# LKS2024_ESP_ACController_v66.net
KiCad netlist of a schematic drawn in EAGLE
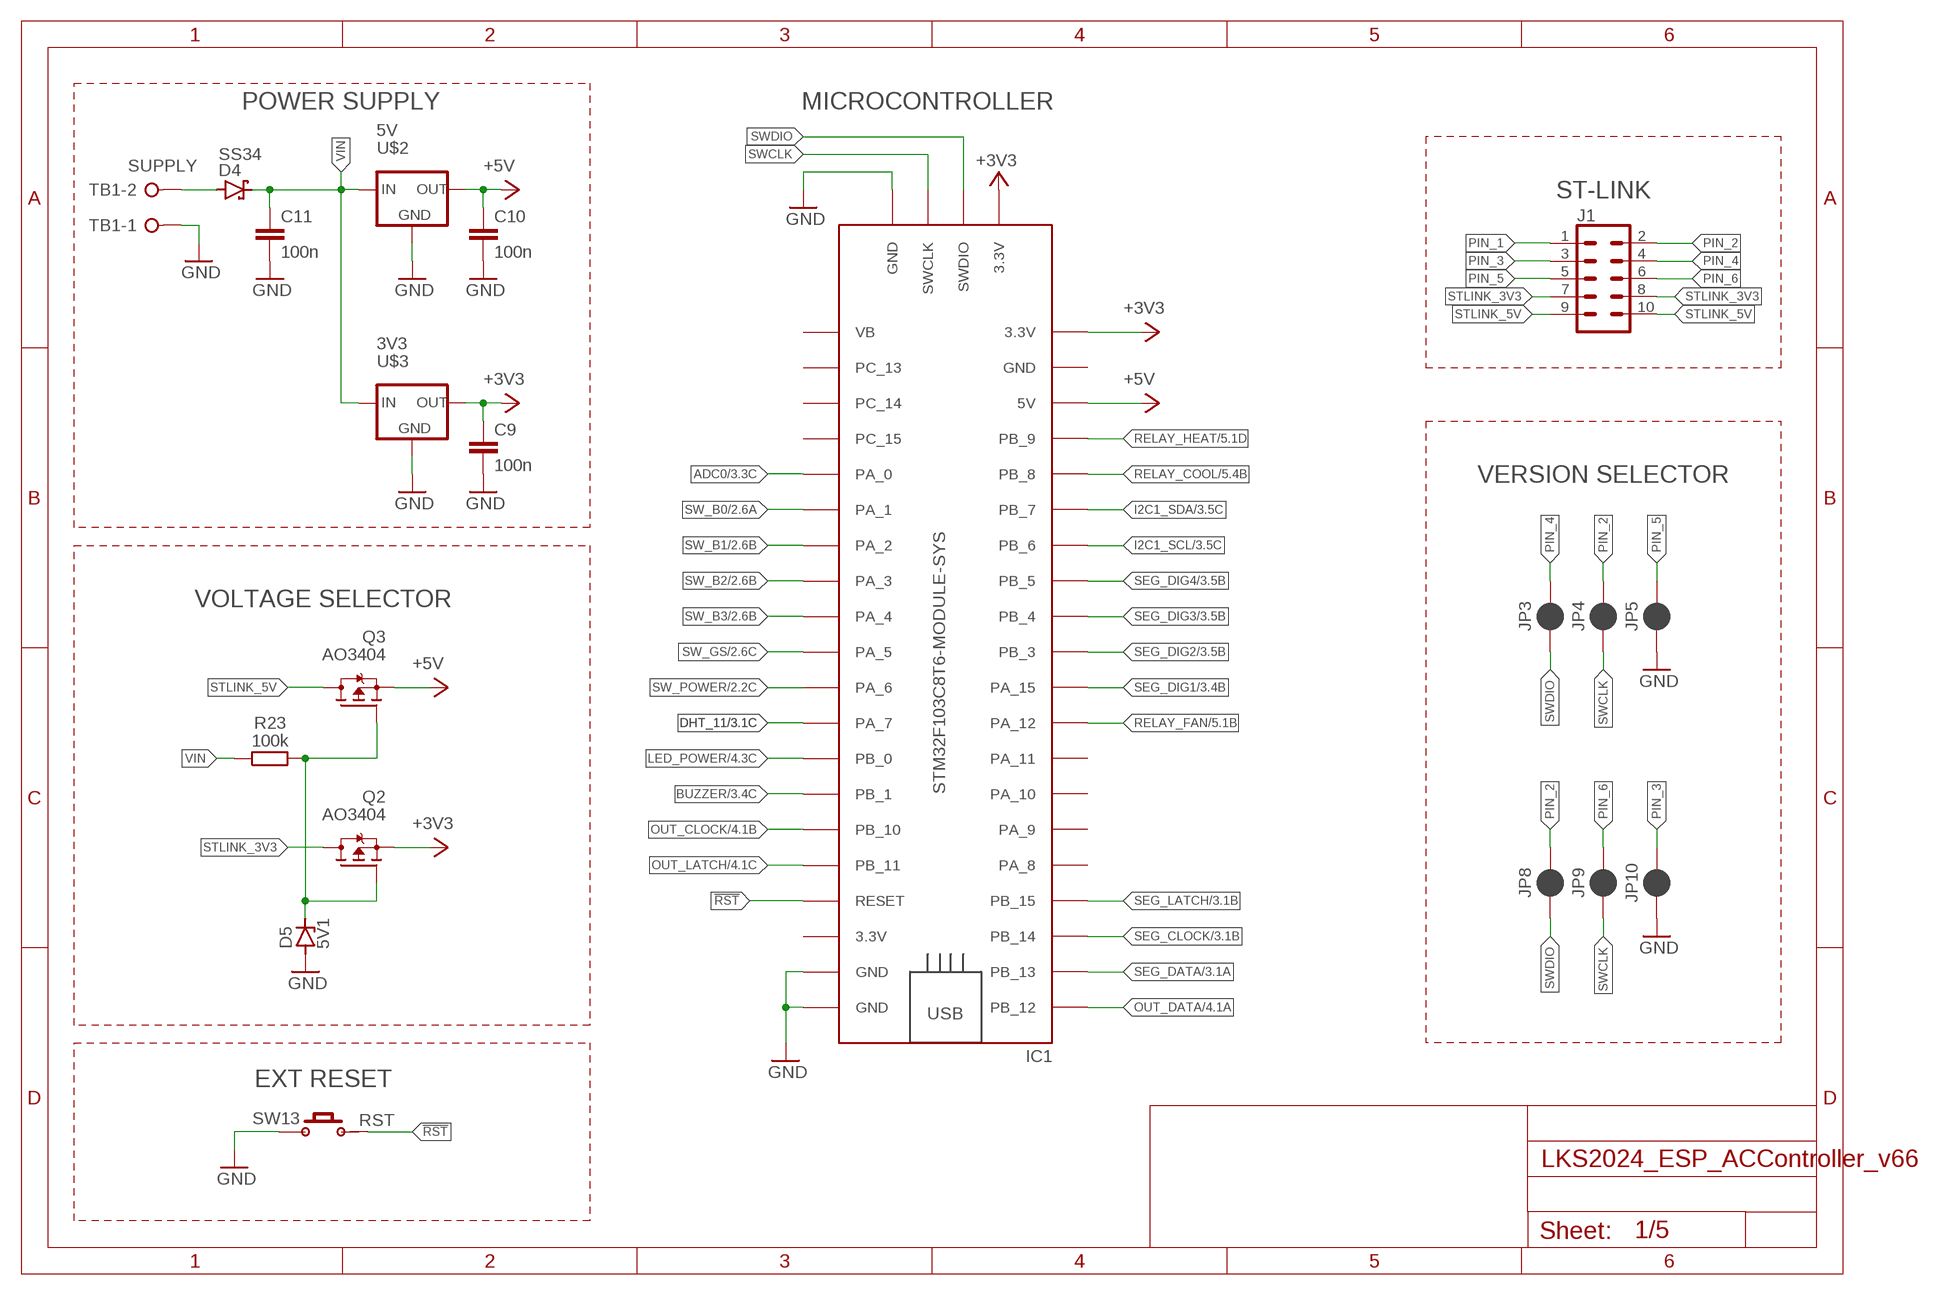
[diagram p0: schematic, sheet 1]
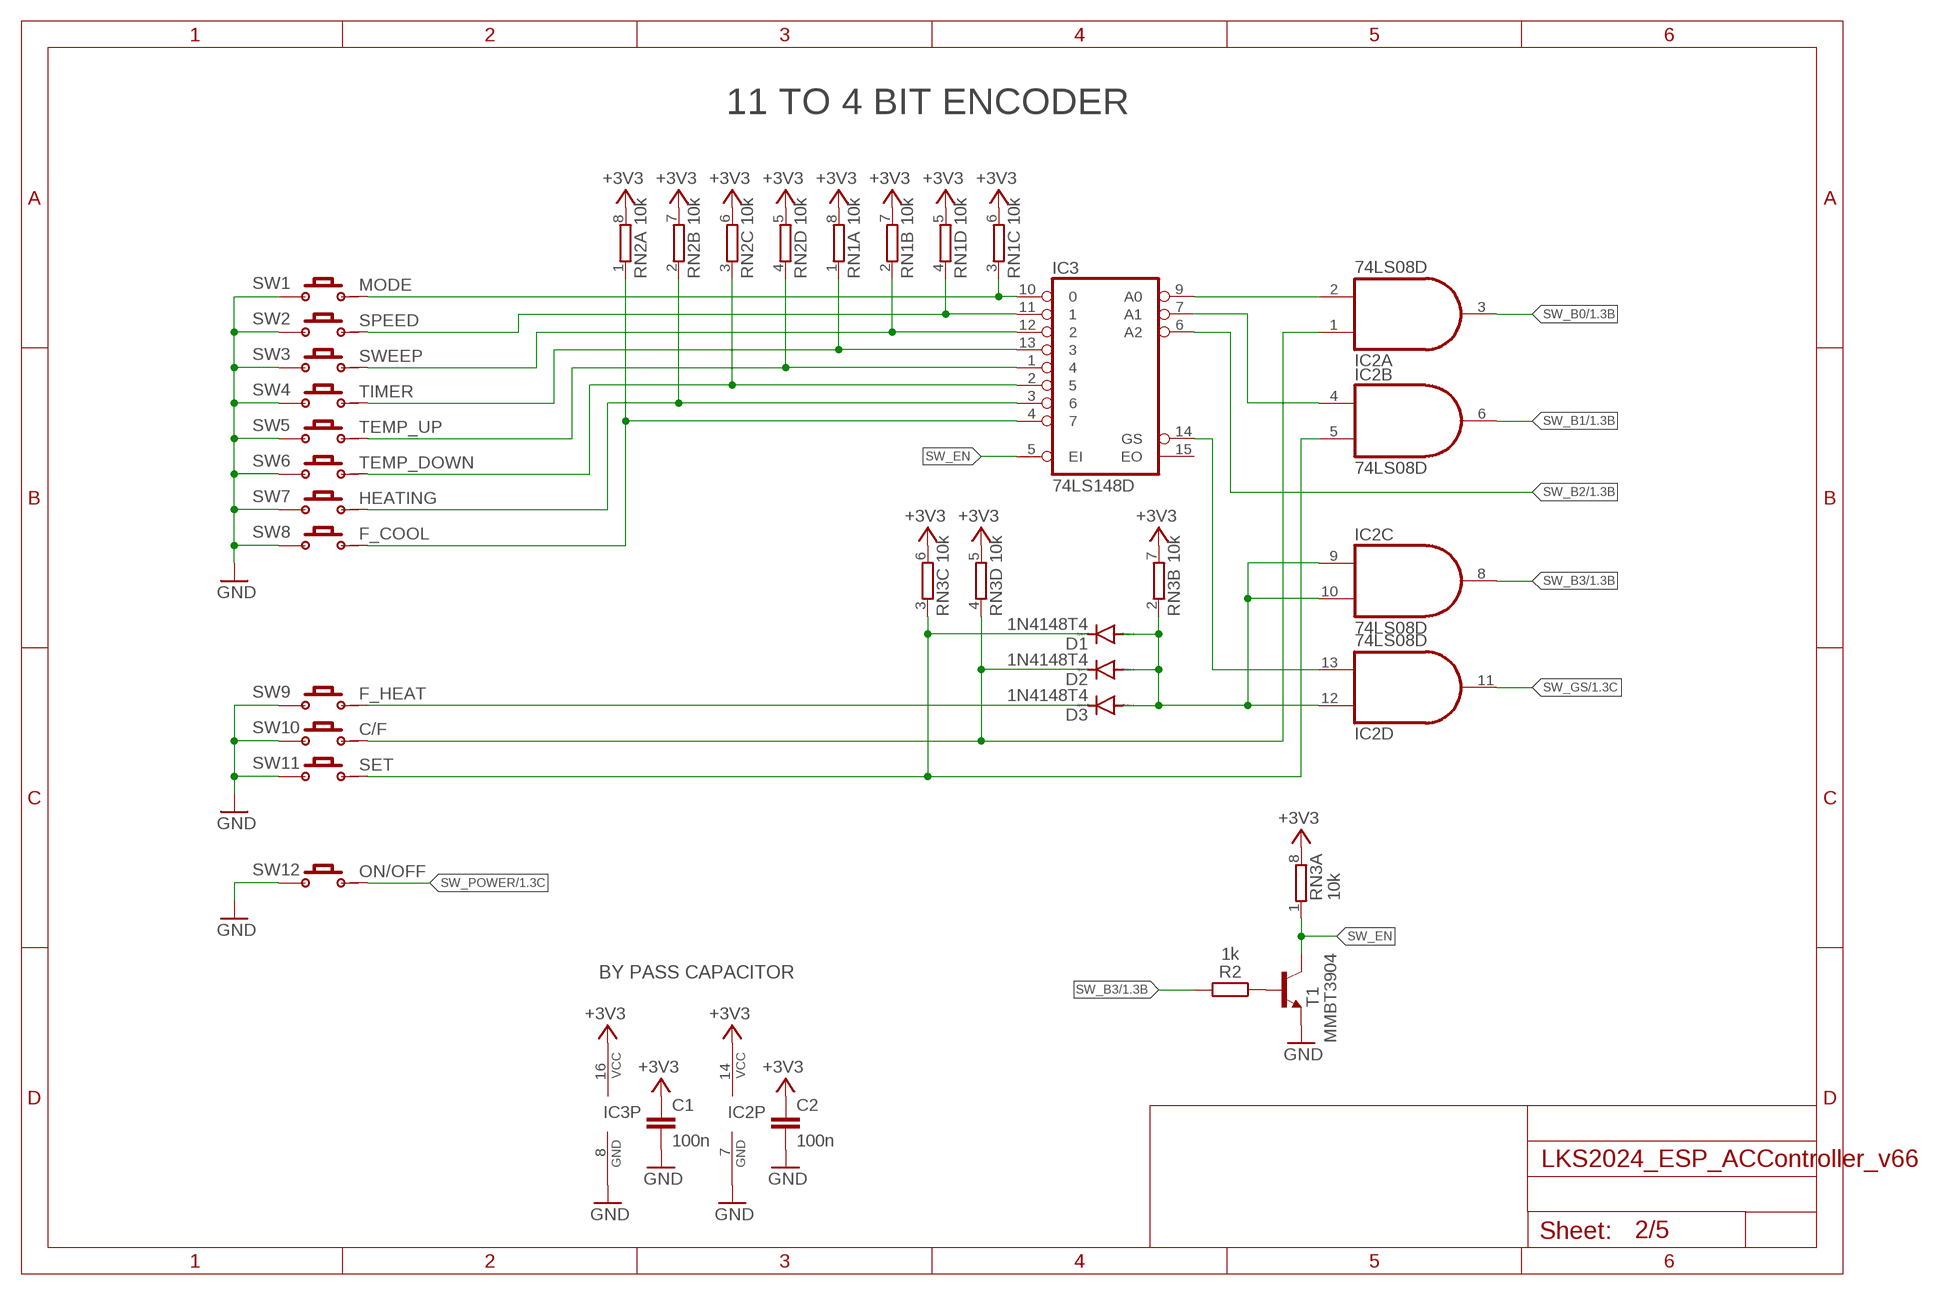
[diagram p1: schematic, sheet 2]
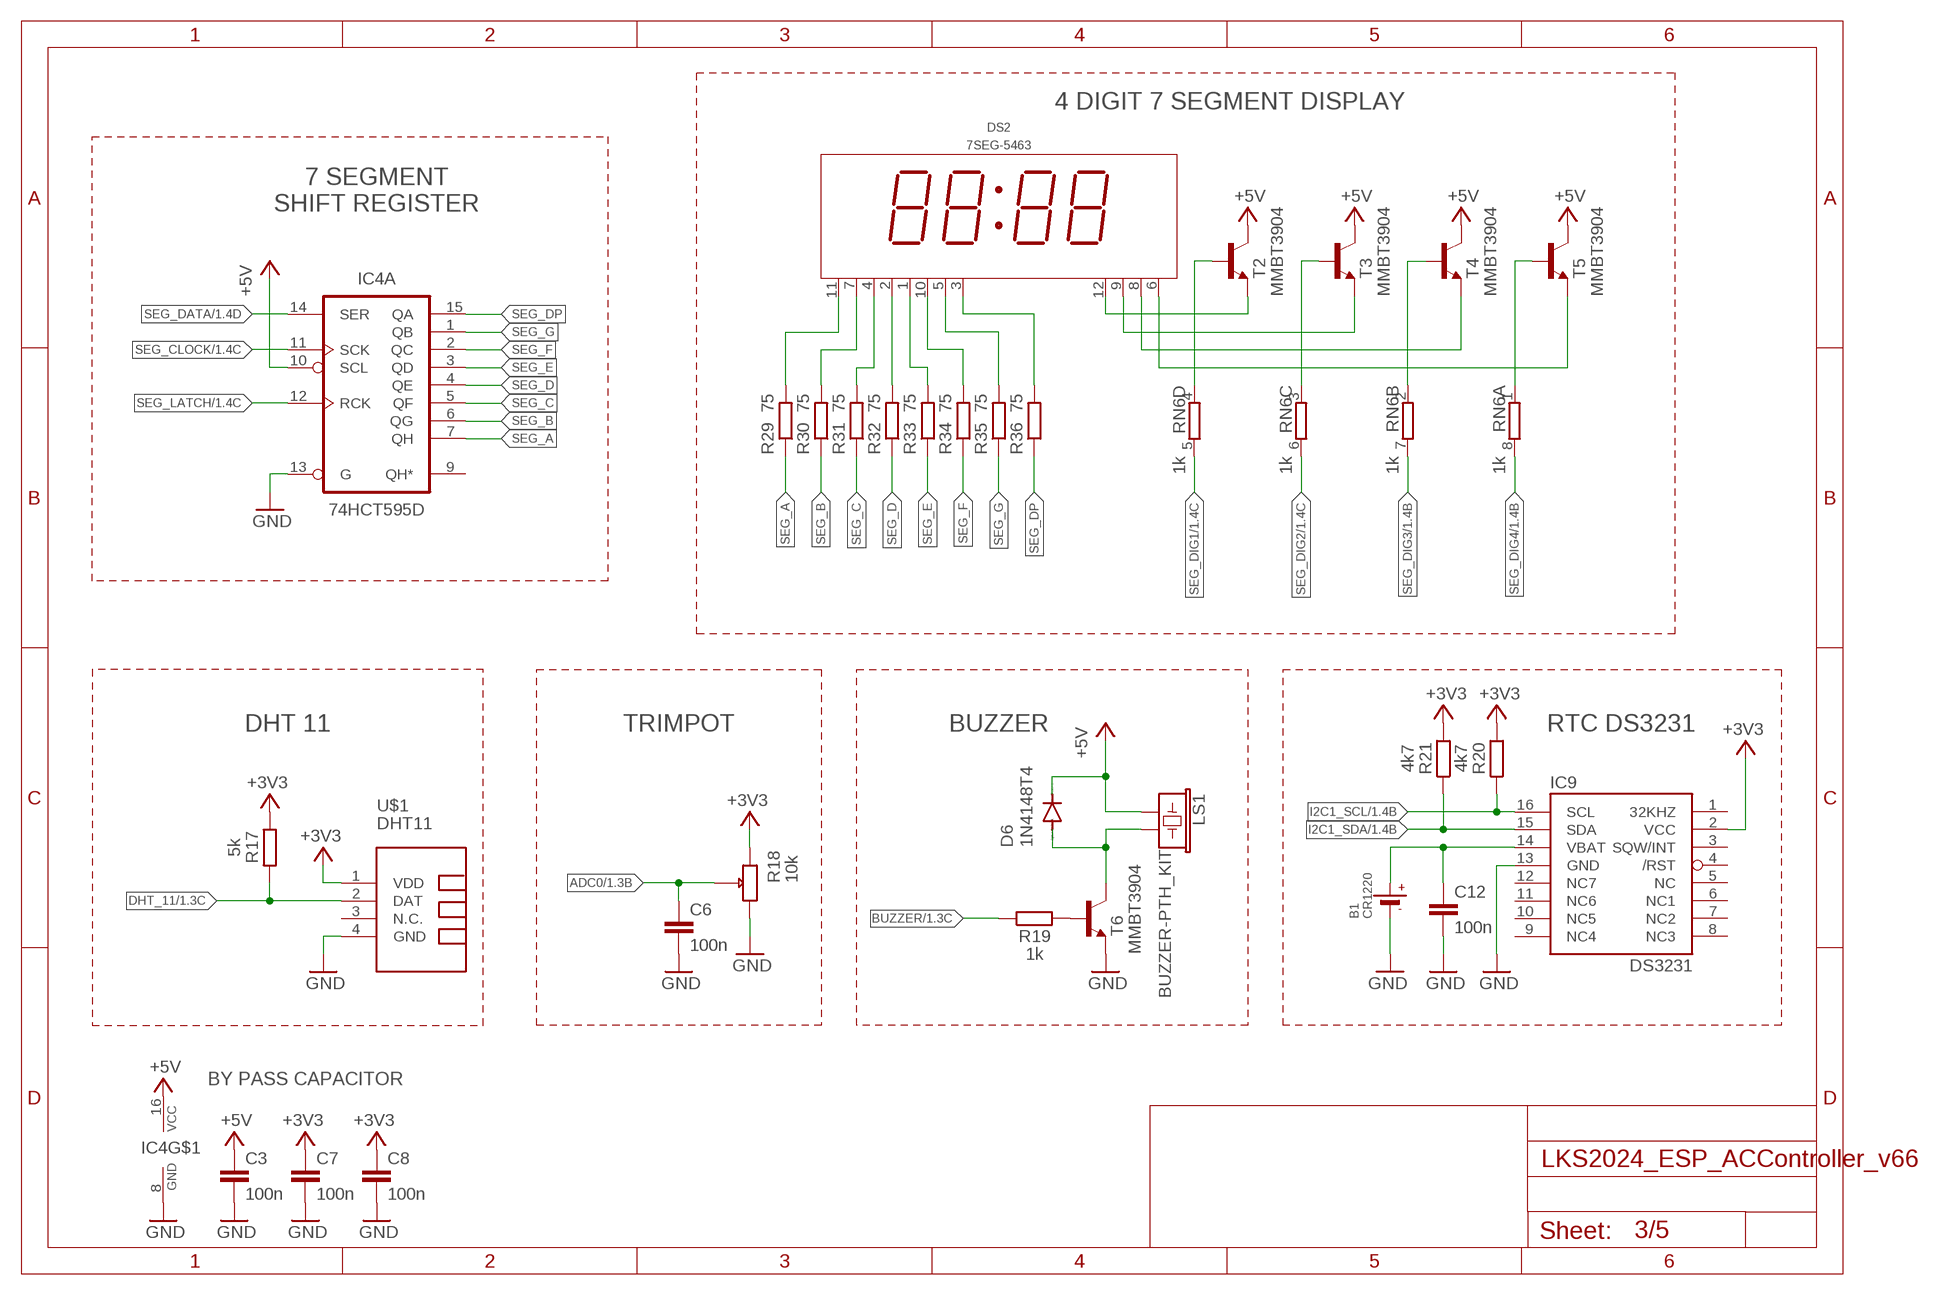
[diagram p2: schematic, sheet 3]
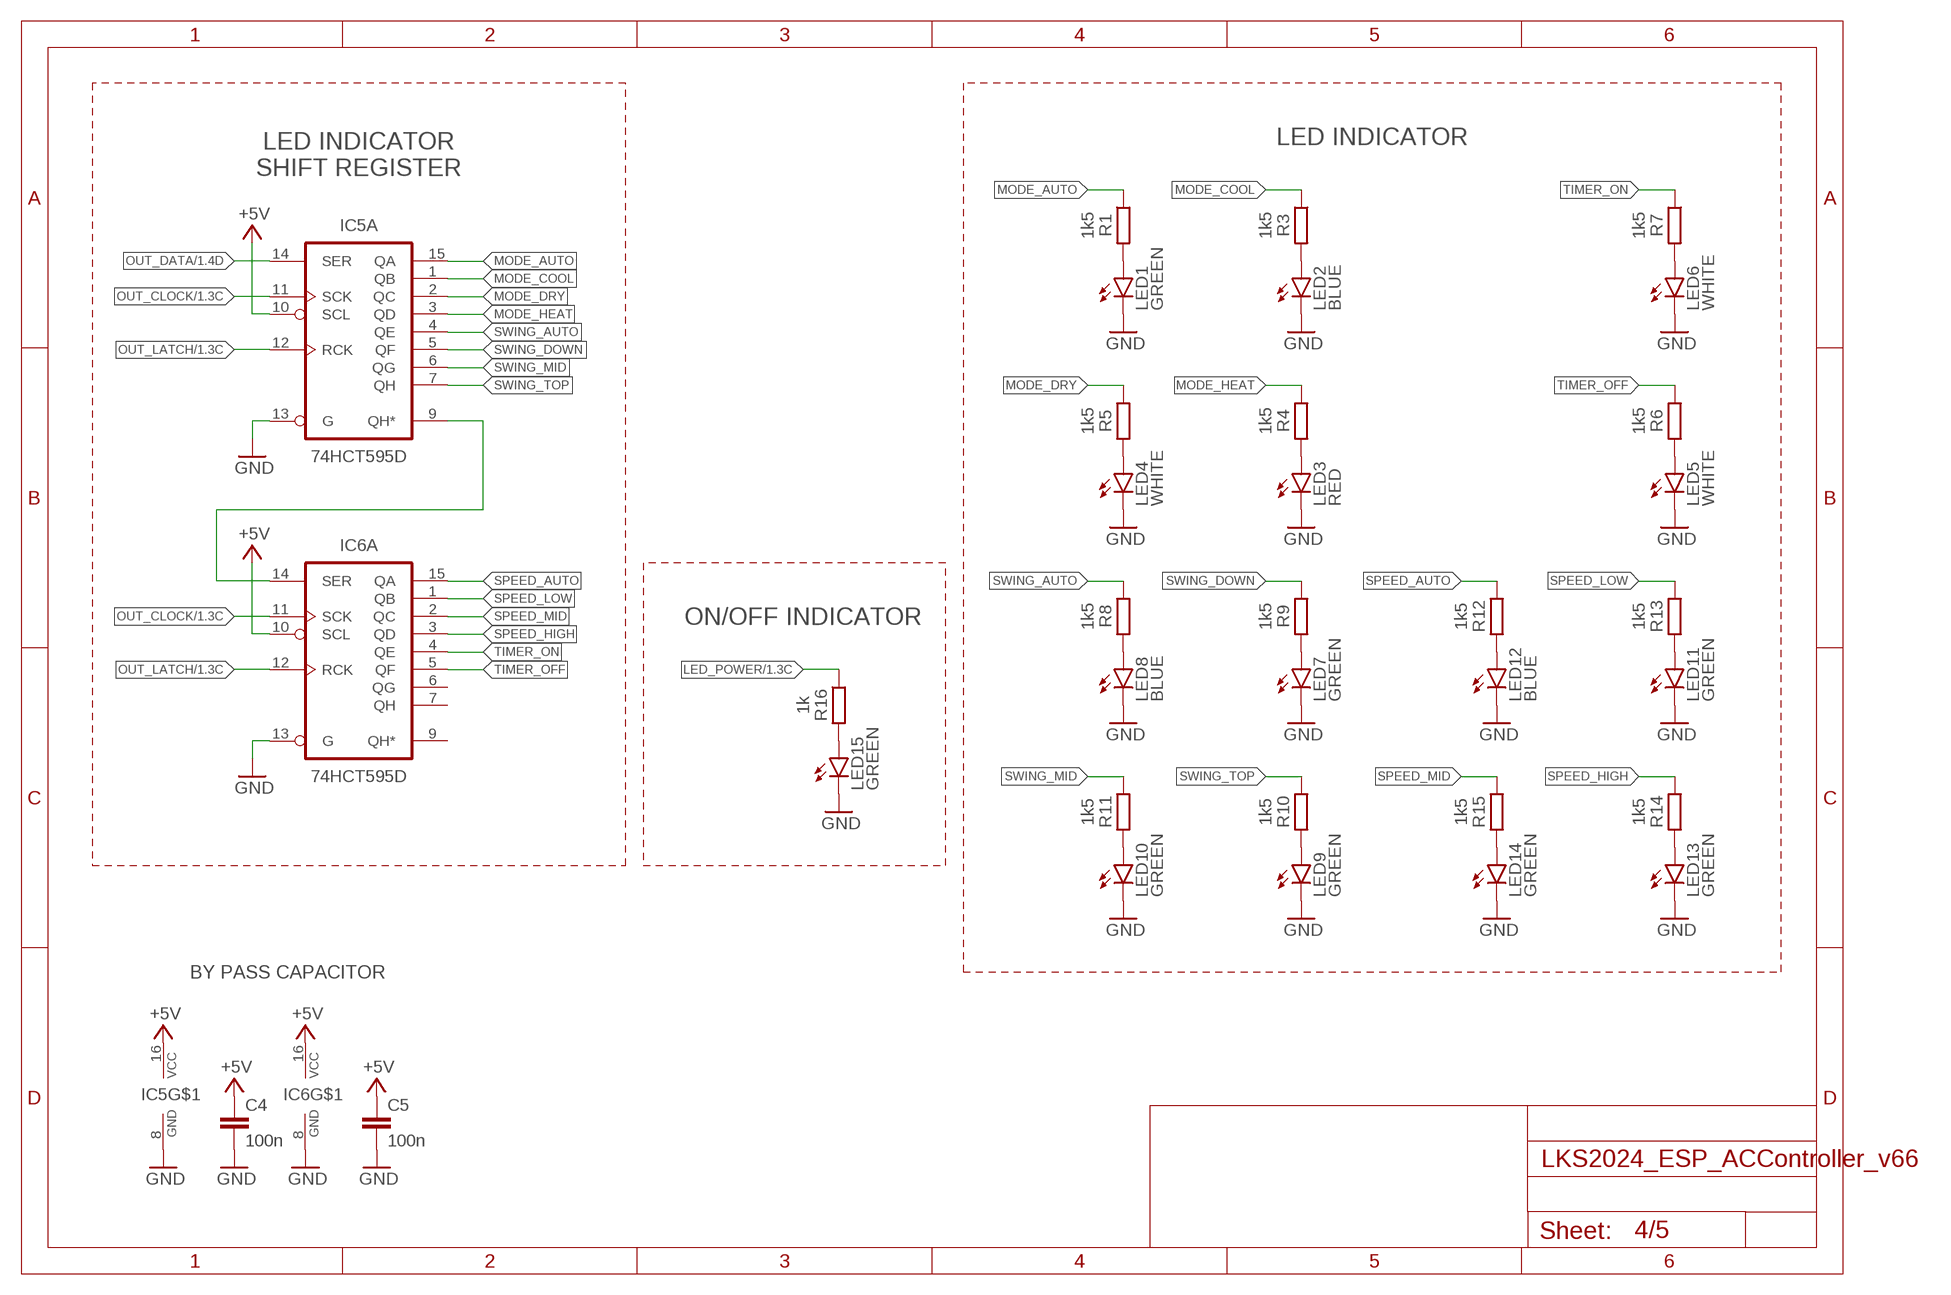
[diagram p3: schematic, sheet 4]
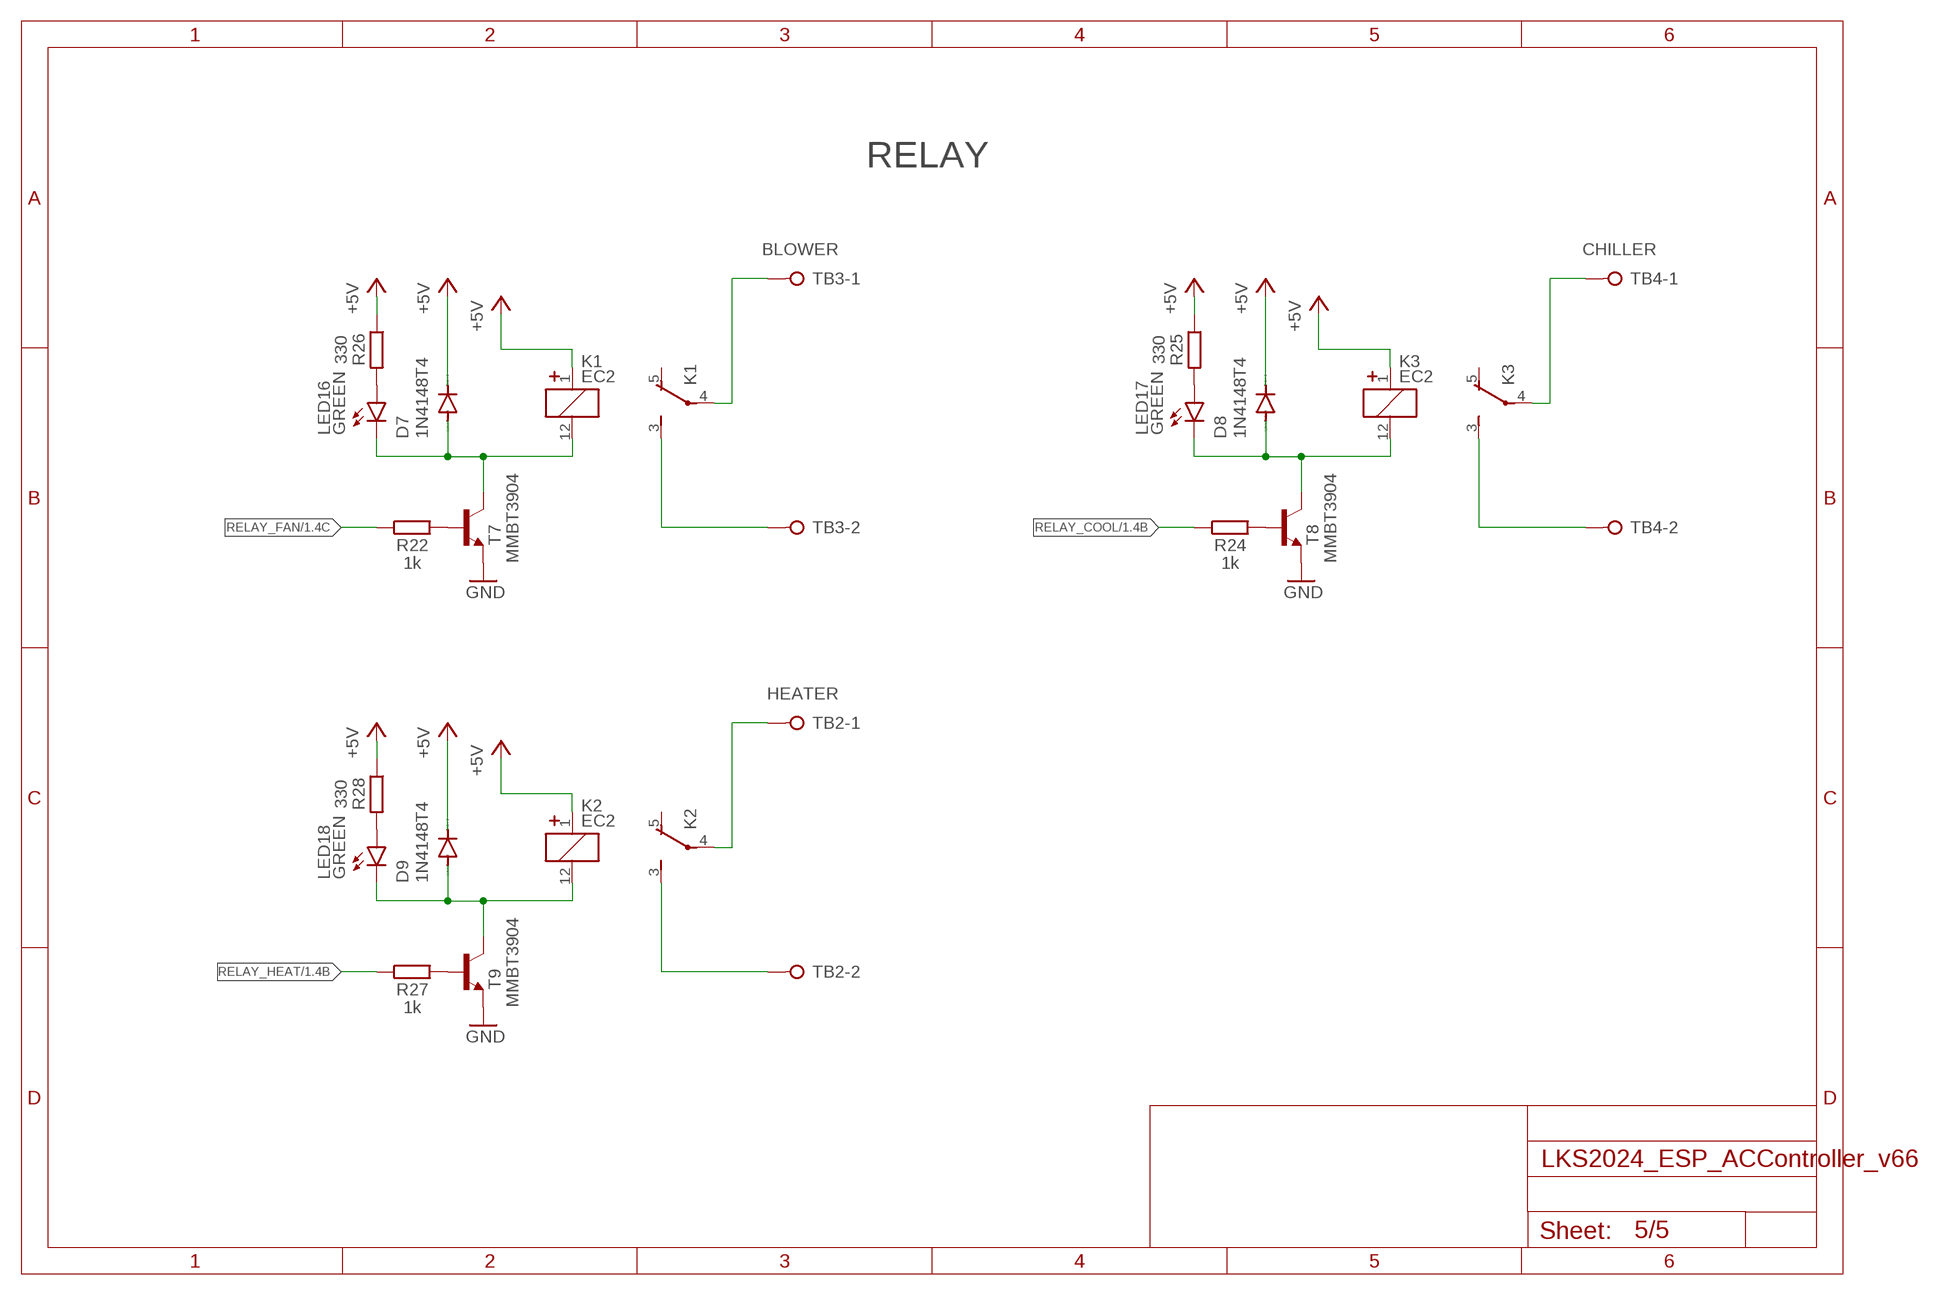
[diagram p4: schematic, sheet 5]

(export (version "E")
  (design (tool "Eeschema 10.0.6"))
  (components
    (comp (ref "D7")
      (value "1N4148T4")
      (footprint "eagle-import:SOD123")
      (libsource (lib "eagle-import") (part "1N4148T4"))
    )
    (comp (ref "D8")
      (value "1N4148T4")
      (footprint "eagle-import:SOD123")
      (libsource (lib "eagle-import") (part "1N4148T4"))
    )
    (comp (ref "D9")
      (value "1N4148T4")
      (footprint "eagle-import:SOD123")
      (libsource (lib "eagle-import") (part "1N4148T4"))
    )
    (comp (ref "K1")
      (value "EC2")
      (footprint "eagle-import:EC2")
      (libsource (lib "eagle-import") (part "EC2"))
    )
    (comp (ref "K2")
      (value "EC2")
      (footprint "eagle-import:EC2")
      (libsource (lib "eagle-import") (part "EC2"))
    )
    (comp (ref "K3")
      (value "EC2")
      (footprint "eagle-import:EC2")
      (libsource (lib "eagle-import") (part "EC2"))
    )
    (comp (ref "LED16")
      (value "GREEN")
      (footprint "eagle-import:CHIPLED_1206")
      (libsource (lib "eagle-import") (part "LEDCHIPLED_1206"))
    )
    (comp (ref "LED17")
      (value "GREEN")
      (footprint "eagle-import:CHIPLED_1206")
      (libsource (lib "eagle-import") (part "LEDCHIPLED_1206"))
    )
    (comp (ref "LED18")
      (value "GREEN")
      (footprint "eagle-import:CHIPLED_1206")
      (libsource (lib "eagle-import") (part "LEDCHIPLED_1206"))
    )
    (comp (ref "R22")
      (value "1k")
      (footprint "eagle-import:R0805")
      (libsource (lib "eagle-import") (part "R-EU_R0805"))
    )
    (comp (ref "R24")
      (value "1k")
      (footprint "eagle-import:R0805")
      (libsource (lib "eagle-import") (part "R-EU_R0805"))
    )
    (comp (ref "R25")
      (value "330")
      (footprint "eagle-import:R0805")
      (libsource (lib "eagle-import") (part "R-EU_R0805"))
    )
    (comp (ref "R26")
      (value "330")
      (footprint "eagle-import:R0805")
      (libsource (lib "eagle-import") (part "R-EU_R0805"))
    )
    (comp (ref "R27")
      (value "1k")
      (footprint "eagle-import:R0805")
      (libsource (lib "eagle-import") (part "R-EU_R0805"))
    )
    (comp (ref "R28")
      (value "330")
      (footprint "eagle-import:R0805")
      (libsource (lib "eagle-import") (part "R-EU_R0805"))
    )
    (comp (ref "T7")
      (value "MMBT3904")
      (footprint "eagle-import:SOT23-BEC")
      (libsource (lib "eagle-import") (part "MMBT3904SOT23-BEC"))
    )
    (comp (ref "T8")
      (value "MMBT3904")
      (footprint "eagle-import:SOT23-BEC")
      (libsource (lib "eagle-import") (part "MMBT3904SOT23-BEC"))
    )
    (comp (ref "T9")
      (value "MMBT3904")
      (footprint "eagle-import:SOT23-BEC")
      (libsource (lib "eagle-import") (part "MMBT3904SOT23-BEC"))
    )
    (comp (ref "TB2")
      (value "HEATER")
      (footprint "eagle-import:MSTBA2")
      (libsource (lib "eagle-import") (part "TERMINAL-BLOK-90"))
    )
    (comp (ref "TB3")
      (value "BLOWER")
      (footprint "eagle-import:MSTBA2")
      (libsource (lib "eagle-import") (part "TERMINAL-BLOK-90"))
    )
    (comp (ref "TB4")
      (value "CHILLER")
      (footprint "eagle-import:MSTBA2")
      (libsource (lib "eagle-import") (part "TERMINAL-BLOK-90"))
    )
    (comp (ref "C9")
      (value "100n")
      (footprint "eagle-import:C0805")
      (libsource (lib "eagle-import") (part "C-EUC0805"))
    )
    (comp (ref "C10")
      (value "100n")
      (footprint "eagle-import:C0805")
      (libsource (lib "eagle-import") (part "C-EUC0805"))
    )
    (comp (ref "C11")
      (value "100n")
      (footprint "eagle-import:C0805")
      (libsource (lib "eagle-import") (part "C-EUC0805"))
    )
    (comp (ref "D4")
      (value "SS34")
      (footprint "eagle-import:SMA")
      (libsource (lib "eagle-import") (part "SS34SMA"))
    )
    (comp (ref "D5")
      (value "5V1")
      (footprint "eagle-import:SOD80C")
      (libsource (lib "eagle-import") (part "ZENER-DIODESOD80C"))
    )
    (comp (ref "IC1")
      (value "STM32F103C8T6-MODULE-SYS")
      (footprint "eagle-import:STM32F103C8T6-MODULE-SYS")
      (libsource (lib "eagle-import") (part "STM32F103C8T6-MODULE-SYS"))
    )
    (comp (ref "J1")
      (value "CONN_05X2ML10L")
      (footprint "eagle-import:ML10L")
      (libsource (lib "eagle-import") (part "CONN_05X2ML10L"))
    )
    (comp (ref "JP3")
      (value "JUMPER-SMT_2_NC_PASTE_SILK")
      (footprint "eagle-import:SMT-JUMPER_2_NC_PASTE_SILK")
      (libsource (lib "eagle-import") (part "JUMPER-SMT_2_NC_PASTE_SILK"))
    )
    (comp (ref "JP4")
      (value "JUMPER-SMT_2_NC_PASTE_SILK")
      (footprint "eagle-import:SMT-JUMPER_2_NC_PASTE_SILK")
      (libsource (lib "eagle-import") (part "JUMPER-SMT_2_NC_PASTE_SILK"))
    )
    (comp (ref "JP5")
      (value "JUMPER-SMT_2_NC_PASTE_SILK")
      (footprint "eagle-import:SMT-JUMPER_2_NC_PASTE_SILK")
      (libsource (lib "eagle-import") (part "JUMPER-SMT_2_NC_PASTE_SILK"))
    )
    (comp (ref "JP8")
      (value "JUMPER-SMT_2_NC_PASTE_SILK")
      (footprint "eagle-import:SMT-JUMPER_2_NC_PASTE_SILK")
      (libsource (lib "eagle-import") (part "JUMPER-SMT_2_NC_PASTE_SILK"))
    )
    (comp (ref "JP9")
      (value "JUMPER-SMT_2_NC_PASTE_SILK")
      (footprint "eagle-import:SMT-JUMPER_2_NC_PASTE_SILK")
      (libsource (lib "eagle-import") (part "JUMPER-SMT_2_NC_PASTE_SILK"))
    )
    (comp (ref "JP10")
      (value "JUMPER-SMT_2_NC_PASTE_SILK")
      (footprint "eagle-import:SMT-JUMPER_2_NC_PASTE_SILK")
      (libsource (lib "eagle-import") (part "JUMPER-SMT_2_NC_PASTE_SILK"))
    )
    (comp (ref "Q2")
      (value "AO3404")
      (footprint "eagle-import:SOT23")
      (libsource (lib "eagle-import") (part "AO3404"))
    )
    (comp (ref "Q3")
      (value "AO3404")
      (footprint "eagle-import:SOT23")
      (libsource (lib "eagle-import") (part "AO3404"))
    )
    (comp (ref "R23")
      (value "100k")
      (footprint "eagle-import:R0805")
      (libsource (lib "eagle-import") (part "R-EU_R0805"))
    )
    (comp (ref "SW13")
      (value "RST")
      (footprint "eagle-import:PUSH_BUTTON_2P")
      (libsource (lib "eagle-import") (part "PUSH_BUTTON2P"))
    )
    (comp (ref "TB1")
      (value "SUPPLY")
      (footprint "eagle-import:MSTBA2")
      (libsource (lib "eagle-import") (part "TERMINAL-BLOK-90"))
    )
    (comp (ref "U$2")
      (value "5V")
      (footprint "eagle-import:SOT223")
      (libsource (lib "eagle-import") (part "V_REG_LD1117VXXLD1117-SMD"))
    )
    (comp (ref "U$3")
      (value "3V3")
      (footprint "eagle-import:SOT223")
      (libsource (lib "eagle-import") (part "V_REG_LD1117VXXLD1117-SMD"))
    )
    (comp (ref "C4")
      (value "100n")
      (footprint "eagle-import:C0805")
      (libsource (lib "eagle-import") (part "C-EUC0805"))
    )
    (comp (ref "C5")
      (value "100n")
      (footprint "eagle-import:C0805")
      (libsource (lib "eagle-import") (part "C-EUC0805"))
    )
    (comp (ref "IC5")
      (value "74HCT595D")
      (footprint "eagle-import:SO16")
      (libsource (lib "eagle-import") (part "74595DHCT"))
    )
    (comp (ref "IC6")
      (value "74HCT595D")
      (footprint "eagle-import:SO16")
      (libsource (lib "eagle-import") (part "74595DHCT"))
    )
    (comp (ref "LED1")
      (value "GREEN")
      (footprint "eagle-import:CHIPLED_1206")
      (libsource (lib "eagle-import") (part "LEDCHIPLED_1206"))
    )
    (comp (ref "LED2")
      (value "BLUE")
      (footprint "eagle-import:CHIPLED_1206")
      (libsource (lib "eagle-import") (part "LEDCHIPLED_1206"))
    )
    (comp (ref "LED3")
      (value "RED")
      (footprint "eagle-import:CHIPLED_1206")
      (libsource (lib "eagle-import") (part "LEDCHIPLED_1206"))
    )
    (comp (ref "LED4")
      (value "WHITE")
      (footprint "eagle-import:CHIPLED_1206")
      (libsource (lib "eagle-import") (part "LEDCHIPLED_1206"))
    )
    (comp (ref "LED5")
      (value "WHITE")
      (footprint "eagle-import:CHIPLED_1206")
      (libsource (lib "eagle-import") (part "LEDCHIPLED_1206"))
    )
    (comp (ref "LED6")
      (value "WHITE")
      (footprint "eagle-import:CHIPLED_1206")
      (libsource (lib "eagle-import") (part "LEDCHIPLED_1206"))
    )
    (comp (ref "LED7")
      (value "GREEN")
      (footprint "eagle-import:CHIPLED_1206")
      (libsource (lib "eagle-import") (part "LEDCHIPLED_1206"))
    )
    (comp (ref "LED8")
      (value "BLUE")
      (footprint "eagle-import:CHIPLED_1206")
      (libsource (lib "eagle-import") (part "LEDCHIPLED_1206"))
    )
    (comp (ref "LED9")
      (value "GREEN")
      (footprint "eagle-import:CHIPLED_1206")
      (libsource (lib "eagle-import") (part "LEDCHIPLED_1206"))
    )
    (comp (ref "LED10")
      (value "GREEN")
      (footprint "eagle-import:CHIPLED_1206")
      (libsource (lib "eagle-import") (part "LEDCHIPLED_1206"))
    )
    (comp (ref "LED11")
      (value "GREEN")
      (footprint "eagle-import:CHIPLED_1206")
      (libsource (lib "eagle-import") (part "LEDCHIPLED_1206"))
    )
    (comp (ref "LED12")
      (value "BLUE")
      (footprint "eagle-import:CHIPLED_1206")
      (libsource (lib "eagle-import") (part "LEDCHIPLED_1206"))
    )
    (comp (ref "LED13")
      (value "GREEN")
      (footprint "eagle-import:CHIPLED_1206")
      (libsource (lib "eagle-import") (part "LEDCHIPLED_1206"))
    )
    (comp (ref "LED14")
      (value "GREEN")
      (footprint "eagle-import:CHIPLED_1206")
      (libsource (lib "eagle-import") (part "LEDCHIPLED_1206"))
    )
    (comp (ref "LED15")
      (value "GREEN")
      (footprint "eagle-import:CHIPLED_1206")
      (libsource (lib "eagle-import") (part "LEDCHIPLED_1206"))
    )
    (comp (ref "R1")
      (value "1k5")
      (footprint "eagle-import:R0805")
      (libsource (lib "eagle-import") (part "R-EU_R0805"))
    )
    (comp (ref "R3")
      (value "1k5")
      (footprint "eagle-import:R0805")
      (libsource (lib "eagle-import") (part "R-EU_R0805"))
    )
    (comp (ref "R4")
      (value "1k5")
      (footprint "eagle-import:R0805")
      (libsource (lib "eagle-import") (part "R-EU_R0805"))
    )
    (comp (ref "R5")
      (value "1k5")
      (footprint "eagle-import:R0805")
      (libsource (lib "eagle-import") (part "R-EU_R0805"))
    )
    (comp (ref "R6")
      (value "1k5")
      (footprint "eagle-import:R0805")
      (libsource (lib "eagle-import") (part "R-EU_R0805"))
    )
    (comp (ref "R7")
      (value "1k5")
      (footprint "eagle-import:R0805")
      (libsource (lib "eagle-import") (part "R-EU_R0805"))
    )
    (comp (ref "R8")
      (value "1k5")
      (footprint "eagle-import:R0805")
      (libsource (lib "eagle-import") (part "R-EU_R0805"))
    )
    (comp (ref "R9")
      (value "1k5")
      (footprint "eagle-import:R0805")
      (libsource (lib "eagle-import") (part "R-EU_R0805"))
    )
    (comp (ref "R10")
      (value "1k5")
      (footprint "eagle-import:R0805")
      (libsource (lib "eagle-import") (part "R-EU_R0805"))
    )
    (comp (ref "R11")
      (value "1k5")
      (footprint "eagle-import:R0805")
      (libsource (lib "eagle-import") (part "R-EU_R0805"))
    )
    (comp (ref "R12")
      (value "1k5")
      (footprint "eagle-import:R0805")
      (libsource (lib "eagle-import") (part "R-EU_R0805"))
    )
    (comp (ref "R13")
      (value "1k5")
      (footprint "eagle-import:R0805")
      (libsource (lib "eagle-import") (part "R-EU_R0805"))
    )
    (comp (ref "R14")
      (value "1k5")
      (footprint "eagle-import:R0805")
      (libsource (lib "eagle-import") (part "R-EU_R0805"))
    )
    (comp (ref "R15")
      (value "1k5")
      (footprint "eagle-import:R0805")
      (libsource (lib "eagle-import") (part "R-EU_R0805"))
    )
    (comp (ref "R16")
      (value "1k")
      (footprint "eagle-import:R0805")
      (libsource (lib "eagle-import") (part "R-EU_R0805"))
    )
    (comp (ref "C1")
      (value "100n")
      (footprint "eagle-import:C0805")
      (libsource (lib "eagle-import") (part "C-EUC0805"))
    )
    (comp (ref "C2")
      (value "100n")
      (footprint "eagle-import:C0805")
      (libsource (lib "eagle-import") (part "C-EUC0805"))
    )
    (comp (ref "D1")
      (value "1N4148T4")
      (footprint "eagle-import:SOD123")
      (libsource (lib "eagle-import") (part "1N4148T4"))
    )
    (comp (ref "D2")
      (value "1N4148T4")
      (footprint "eagle-import:SOD123")
      (libsource (lib "eagle-import") (part "1N4148T4"))
    )
    (comp (ref "D3")
      (value "1N4148T4")
      (footprint "eagle-import:SOD123")
      (libsource (lib "eagle-import") (part "1N4148T4"))
    )
    (comp (ref "IC2")
      (value "74LS08D")
      (footprint "eagle-import:SO14")
      (libsource (lib "eagle-import") (part "7408DLS"))
    )
    (comp (ref "IC3")
      (value "74LS148D")
      (footprint "eagle-import:SO16")
      (libsource (lib "eagle-import") (part "74148DLS"))
    )
    (comp (ref "R2")
      (value "1k")
      (footprint "eagle-import:R0805")
      (libsource (lib "eagle-import") (part "R-EU_R0805"))
    )
    (comp (ref "RN1")
      (value "10k")
      (footprint "eagle-import:0603-ARC")
      (libsource (lib "eagle-import") (part "4R-N0603-ARC"))
    )
    (comp (ref "RN2")
      (value "10k")
      (footprint "eagle-import:0603-ARC")
      (libsource (lib "eagle-import") (part "4R-N0603-ARC"))
    )
    (comp (ref "RN3")
      (value "10k")
      (footprint "eagle-import:0603-ARC")
      (libsource (lib "eagle-import") (part "4R-N0603-ARC"))
    )
    (comp (ref "SW1")
      (value "MODE")
      (footprint "eagle-import:PUSH_BUTTON_2P")
      (libsource (lib "eagle-import") (part "PUSH_BUTTON2P"))
    )
    (comp (ref "SW2")
      (value "SPEED")
      (footprint "eagle-import:PUSH_BUTTON_2P")
      (libsource (lib "eagle-import") (part "PUSH_BUTTON2P"))
    )
    (comp (ref "SW3")
      (value "SWEEP")
      (footprint "eagle-import:PUSH_BUTTON_2P")
      (libsource (lib "eagle-import") (part "PUSH_BUTTON2P"))
    )
    (comp (ref "SW4")
      (value "TIMER")
      (footprint "eagle-import:PUSH_BUTTON_2P")
      (libsource (lib "eagle-import") (part "PUSH_BUTTON2P"))
    )
    (comp (ref "SW5")
      (value "TEMP_UP")
      (footprint "eagle-import:PUSH_BUTTON_2P")
      (libsource (lib "eagle-import") (part "PUSH_BUTTON2P"))
    )
    (comp (ref "SW6")
      (value "TEMP_DOWN")
      (footprint "eagle-import:PUSH_BUTTON_2P")
      (libsource (lib "eagle-import") (part "PUSH_BUTTON2P"))
    )
    (comp (ref "SW7")
      (value "HEATING")
      (footprint "eagle-import:PUSH_BUTTON_2P")
      (libsource (lib "eagle-import") (part "PUSH_BUTTON2P"))
    )
    (comp (ref "SW8")
      (value "F_COOL")
      (footprint "eagle-import:PUSH_BUTTON_2P")
      (libsource (lib "eagle-import") (part "PUSH_BUTTON2P"))
    )
    (comp (ref "SW9")
      (value "F_HEAT")
      (footprint "eagle-import:PUSH_BUTTON_2P")
      (libsource (lib "eagle-import") (part "PUSH_BUTTON2P"))
    )
    (comp (ref "SW10")
      (value "C/F")
      (footprint "eagle-import:PUSH_BUTTON_2P")
      (libsource (lib "eagle-import") (part "PUSH_BUTTON2P"))
    )
    (comp (ref "SW11")
      (value "SET")
      (footprint "eagle-import:PUSH_BUTTON_2P")
      (libsource (lib "eagle-import") (part "PUSH_BUTTON2P"))
    )
    (comp (ref "SW12")
      (value "ON/OFF")
      (footprint "eagle-import:PUSH_BUTTON_2P")
      (libsource (lib "eagle-import") (part "PUSH_BUTTON2P"))
    )
    (comp (ref "T1")
      (value "MMBT3904")
      (footprint "eagle-import:SOT23-BEC")
      (libsource (lib "eagle-import") (part "MMBT3904SOT23-BEC"))
    )
    (comp (ref "B1")
      (value "CR1220")
      (footprint "eagle-import:CR1220")
      (libsource (lib "eagle-import") (part "BATTERY"))
    )
    (comp (ref "C3")
      (value "100n")
      (footprint "eagle-import:C0805")
      (libsource (lib "eagle-import") (part "C-EUC0805"))
    )
    (comp (ref "C6")
      (value "100n")
      (footprint "eagle-import:C0805")
      (libsource (lib "eagle-import") (part "C-EUC0805"))
    )
    (comp (ref "C7")
      (value "100n")
      (footprint "eagle-import:C0805")
      (libsource (lib "eagle-import") (part "C-EUC0805"))
    )
    (comp (ref "C8")
      (value "100n")
      (footprint "eagle-import:C0805")
      (libsource (lib "eagle-import") (part "C-EUC0805"))
    )
    (comp (ref "C12")
      (value "100n")
      (footprint "eagle-import:C0805")
      (libsource (lib "eagle-import") (part "C-EUC0805"))
    )
    (comp (ref "D6")
      (value "1N4148T4")
      (footprint "eagle-import:SOD123")
      (libsource (lib "eagle-import") (part "1N4148T4"))
    )
    (comp (ref "DS2")
      (value "7SEG-5463")
      (footprint "eagle-import:5643")
      (libsource (lib "eagle-import") (part "7SEG-5463"))
    )
    (comp (ref "IC4")
      (value "74HCT595D")
      (footprint "eagle-import:SO16")
      (libsource (lib "eagle-import") (part "74595DHCT"))
    )
    (comp (ref "IC9")
      (value "DS3231\"")
      (footprint "eagle-import:SO16W")
      (libsource (lib "eagle-import") (part "DS3231{dblquote}"))
    )
    (comp (ref "LS1")
      (value "BUZZER-PTH_KIT")
      (footprint "eagle-import:BUZZER-12MM-KIT")
      (libsource (lib "eagle-import") (part "BUZZER-PTH_KIT"))
    )
    (comp (ref "R17")
      (value "5k")
      (footprint "eagle-import:R0805")
      (libsource (lib "eagle-import") (part "R-EU_R0805"))
    )
    (comp (ref "R18")
      (value "10k")
      (footprint "eagle-import:TRIM_3386P-1-101T")
      (fields (field (name "MF") "Bourns") (field (name "MP") "3386P-1-101"))
      (libsource (lib "eagle-import") (part "3386P-1-101T"))
    )
    (comp (ref "R19")
      (value "1k")
      (footprint "eagle-import:R0805")
      (libsource (lib "eagle-import") (part "R-EU_R0805"))
    )
    (comp (ref "R20")
      (value "4k7")
      (footprint "eagle-import:R0805")
      (libsource (lib "eagle-import") (part "R-EU_R0805"))
    )
    (comp (ref "R21")
      (value "4k7")
      (footprint "eagle-import:R0805")
      (libsource (lib "eagle-import") (part "R-EU_R0805"))
    )
    (comp (ref "R29")
      (value "75")
      (footprint "eagle-import:R0603")
      (libsource (lib "eagle-import") (part "R-EU_R0603"))
    )
    (comp (ref "R30")
      (value "75")
      (footprint "eagle-import:R0603")
      (libsource (lib "eagle-import") (part "R-EU_R0603"))
    )
    (comp (ref "R31")
      (value "75")
      (footprint "eagle-import:R0603")
      (libsource (lib "eagle-import") (part "R-EU_R0603"))
    )
    (comp (ref "R32")
      (value "75")
      (footprint "eagle-import:R0603")
      (libsource (lib "eagle-import") (part "R-EU_R0603"))
    )
    (comp (ref "R33")
      (value "75")
      (footprint "eagle-import:R0603")
      (libsource (lib "eagle-import") (part "R-EU_R0603"))
    )
    (comp (ref "R34")
      (value "75")
      (footprint "eagle-import:R0603")
      (libsource (lib "eagle-import") (part "R-EU_R0603"))
    )
    (comp (ref "R35")
      (value "75")
      (footprint "eagle-import:R0603")
      (libsource (lib "eagle-import") (part "R-EU_R0603"))
    )
    (comp (ref "R36")
      (value "75")
      (footprint "eagle-import:R0603")
      (libsource (lib "eagle-import") (part "R-EU_R0603"))
    )
    (comp (ref "RN6")
      (value "1k")
      (footprint "eagle-import:0603-ARC")
      (libsource (lib "eagle-import") (part "4R-N0603-ARC"))
    )
    (comp (ref "T2")
      (value "MMBT3904")
      (footprint "eagle-import:SOT23-BEC")
      (libsource (lib "eagle-import") (part "MMBT3904SOT23-BEC"))
    )
    (comp (ref "T3")
      (value "MMBT3904")
      (footprint "eagle-import:SOT23-BEC")
      (libsource (lib "eagle-import") (part "MMBT3904SOT23-BEC"))
    )
    (comp (ref "T4")
      (value "MMBT3904")
      (footprint "eagle-import:SOT23-BEC")
      (libsource (lib "eagle-import") (part "MMBT3904SOT23-BEC"))
    )
    (comp (ref "T5")
      (value "MMBT3904")
      (footprint "eagle-import:SOT23-BEC")
      (libsource (lib "eagle-import") (part "MMBT3904SOT23-BEC"))
    )
    (comp (ref "T6")
      (value "MMBT3904")
      (footprint "eagle-import:SOT23-BEC")
      (libsource (lib "eagle-import") (part "MMBT3904SOT23-BEC"))
    )
    (comp (ref "U$1")
      (value "DHT11")
      (footprint "eagle-import:DHT11")
      (libsource (lib "eagle-import") (part "TEMP-HUM-SENSOR-DHT11H"))
    )
  )
  (nets
    (net (code "1") (name "+3V3") (class "Default")
      (node (ref "C1") (pin "1") (pinfunction "1_1") (pintype "passive"))
      (node (ref "C2") (pin "1") (pinfunction "1_1") (pintype "passive"))
      (node (ref "C7") (pin "1") (pinfunction "1_1") (pintype "passive"))
      (node (ref "C8") (pin "1") (pinfunction "1_1") (pintype "passive"))
      (node (ref "C9") (pin "1") (pinfunction "1_1") (pintype "passive"))
      (node (ref "IC1") (pin "3.3V_1") (pinfunction "3.3V_3.3V_1") (pintype "bidirectional"))
      (node (ref "IC1") (pin "3V3_1") (pinfunction "3.3V_3V3_1") (pintype "bidirectional"))
      (node (ref "IC1") (pin "3V3_3") (pinfunction "3.3V_3V3_3") (pintype "bidirectional"))
      (node (ref "IC2") (pin "14") (pinfunction "VCC_14") (pintype "power_in"))
      (node (ref "IC3") (pin "16") (pinfunction "VCC_16") (pintype "power_in"))
      (node (ref "IC9") (pin "2") (pinfunction "VCC_2") (pintype "power_in"))
      (node (ref "Q2") (pin "2") (pinfunction "S_2") (pintype "passive"))
      (node (ref "R17") (pin "1") (pinfunction "1_1") (pintype "passive"))
      (node (ref "R18") (pin "3") (pinfunction "CW_3") (pintype "passive"))
      (node (ref "R20") (pin "2") (pinfunction "2_2") (pintype "passive"))
      (node (ref "R21") (pin "2") (pinfunction "2_2") (pintype "passive"))
      (node (ref "RN1") (pin "5") (pinfunction "2_5") (pintype "passive"))
      (node (ref "RN1") (pin "6") (pinfunction "2_6") (pintype "passive"))
      (node (ref "RN1") (pin "7") (pinfunction "2_7") (pintype "passive"))
      (node (ref "RN1") (pin "8") (pinfunction "2_8") (pintype "passive"))
      (node (ref "RN2") (pin "5") (pinfunction "2_5") (pintype "passive"))
      (node (ref "RN2") (pin "6") (pinfunction "2_6") (pintype "passive"))
      (node (ref "RN2") (pin "7") (pinfunction "2_7") (pintype "passive"))
      (node (ref "RN2") (pin "8") (pinfunction "2_8") (pintype "passive"))
      (node (ref "RN3") (pin "5") (pinfunction "2_5") (pintype "passive"))
      (node (ref "RN3") (pin "6") (pinfunction "2_6") (pintype "passive"))
      (node (ref "RN3") (pin "7") (pinfunction "2_7") (pintype "passive"))
      (node (ref "RN3") (pin "8") (pinfunction "2_8") (pintype "passive"))
      (node (ref "U$1") (pin "1") (pinfunction "VDD_1") (pintype "power_in"))
      (node (ref "U$3") (pin "2") (pinfunction "OUT_2") (pintype "passive"))
    )
    (net (code "2") (name "+5V") (class "Default")
      (node (ref "C10") (pin "1") (pinfunction "1_1") (pintype "passive"))
      (node (ref "C3") (pin "1") (pinfunction "1_1") (pintype "passive"))
      (node (ref "C4") (pin "1") (pinfunction "1_1") (pintype "passive"))
      (node (ref "C5") (pin "1") (pinfunction "1_1") (pintype "passive"))
      (node (ref "D6") (pin "C") (pinfunction "C_C") (pintype "passive"))
      (node (ref "D7") (pin "C") (pinfunction "C_C") (pintype "passive"))
      (node (ref "D8") (pin "C") (pinfunction "C_C") (pintype "passive"))
      (node (ref "D9") (pin "C") (pinfunction "C_C") (pintype "passive"))
      (node (ref "IC1") (pin "5V") (pinfunction "5V_5V") (pintype "bidirectional"))
      (node (ref "IC4") (pin "10") (pinfunction "SCL_10") (pintype "input"))
      (node (ref "IC4") (pin "16") (pinfunction "VCC_16") (pintype "power_in"))
      (node (ref "IC5") (pin "10") (pinfunction "SCL_10") (pintype "input"))
      (node (ref "IC5") (pin "16") (pinfunction "VCC_16") (pintype "power_in"))
      (node (ref "IC6") (pin "10") (pinfunction "SCL_10") (pintype "input"))
      (node (ref "IC6") (pin "16") (pinfunction "VCC_16") (pintype "power_in"))
      (node (ref "K1") (pin "1") (pinfunction "1+_1") (pintype "passive"))
      (node (ref "K2") (pin "1") (pinfunction "1+_1") (pintype "passive"))
      (node (ref "K3") (pin "1") (pinfunction "1+_1") (pintype "passive"))
      (node (ref "LS1") (pin "+\\") (pinfunction "1_+\\") (pintype "passive"))
      (node (ref "Q3") (pin "2") (pinfunction "S_2") (pintype "passive"))
      (node (ref "R25") (pin "1") (pinfunction "1_1") (pintype "passive"))
      (node (ref "R26") (pin "1") (pinfunction "1_1") (pintype "passive"))
      (node (ref "R28") (pin "1") (pinfunction "1_1") (pintype "passive"))
      (node (ref "T2") (pin "C") (pinfunction "C_C") (pintype "passive"))
      (node (ref "T3") (pin "C") (pinfunction "C_C") (pintype "passive"))
      (node (ref "T4") (pin "C") (pinfunction "C_C") (pintype "passive"))
      (node (ref "T5") (pin "C") (pinfunction "C_C") (pintype "passive"))
      (node (ref "U$2") (pin "2") (pinfunction "OUT_2") (pintype "passive"))
    )
    (net (code "3") (name "ADC0") (class "Default")
      (node (ref "C6") (pin "1") (pinfunction "1_1") (pintype "passive"))
      (node (ref "IC1") (pin "PA_0") (pinfunction "PA_0_PA_0") (pintype "bidirectional"))
      (node (ref "R18") (pin "2") (pinfunction "WIPER_2") (pintype "passive"))
    )
    (net (code "4") (name "BUZZER") (class "Default")
      (node (ref "IC1") (pin "PB_1") (pinfunction "PB_1_PB_1") (pintype "bidirectional"))
      (node (ref "R19") (pin "1") (pinfunction "1_1") (pintype "passive"))
    )
    (net (code "5") (name "DHT_11") (class "Default")
      (node (ref "IC1") (pin "PA_7") (pinfunction "PA_7_PA_7") (pintype "bidirectional"))
      (node (ref "R17") (pin "2") (pinfunction "2_2") (pintype "passive"))
      (node (ref "U$1") (pin "2") (pinfunction "DAT_2") (pintype "bidirectional"))
    )
    (net (code "6") (name "GND") (class "Default")
      (node (ref "B1") (pin "-") (pinfunction "-_-") (pintype "passive"))
      (node (ref "C1") (pin "2") (pinfunction "2_2") (pintype "passive"))
      (node (ref "C10") (pin "2") (pinfunction "2_2") (pintype "passive"))
      (node (ref "C11") (pin "2") (pinfunction "2_2") (pintype "passive"))
      (node (ref "C12") (pin "2") (pinfunction "2_2") (pintype "passive"))
      (node (ref "C2") (pin "2") (pinfunction "2_2") (pintype "passive"))
      (node (ref "C3") (pin "2") (pinfunction "2_2") (pintype "passive"))
      (node (ref "C4") (pin "2") (pinfunction "2_2") (pintype "passive"))
      (node (ref "C5") (pin "2") (pinfunction "2_2") (pintype "passive"))
      (node (ref "C6") (pin "2") (pinfunction "2_2") (pintype "passive"))
      (node (ref "C7") (pin "2") (pinfunction "2_2") (pintype "passive"))
      (node (ref "C8") (pin "2") (pinfunction "2_2") (pintype "passive"))
      (node (ref "C9") (pin "2") (pinfunction "2_2") (pintype "passive"))
      (node (ref "D5") (pin "A") (pinfunction "A_A") (pintype "passive"))
      (node (ref "IC1") (pin "GND_2") (pinfunction "GND_GND_2") (pintype "bidirectional"))
      (node (ref "IC1") (pin "GND_3") (pinfunction "GND_GND_3") (pintype "power_in"))
      (node (ref "IC1") (pin "GND_4") (pinfunction "GND_GND_4") (pintype "power_in"))
      (node (ref "IC1") (pin "GND_5") (pinfunction "GND_GND_5") (pintype "power_in"))
      (node (ref "IC2") (pin "7") (pinfunction "GND_7") (pintype "power_in"))
      (node (ref "IC3") (pin "8") (pinfunction "GND_8") (pintype "power_in"))
      (node (ref "IC4") (pin "13") (pinfunction "G_13") (pintype "input"))
      (node (ref "IC4") (pin "8") (pinfunction "GND_8") (pintype "power_in"))
      (node (ref "IC5") (pin "13") (pinfunction "G_13") (pintype "input"))
      (node (ref "IC5") (pin "8") (pinfunction "GND_8") (pintype "power_in"))
      (node (ref "IC6") (pin "13") (pinfunction "G_13") (pintype "input"))
      (node (ref "IC6") (pin "8") (pinfunction "GND_8") (pintype "power_in"))
      (node (ref "IC9") (pin "13") (pinfunction "GND_13") (pintype "power_in"))
      (node (ref "JP10") (pin "1") (pinfunction "1_1") (pintype "passive"))
      (node (ref "JP5") (pin "1") (pinfunction "1_1") (pintype "passive"))
      (node (ref "LED1") (pin "C") (pinfunction "C_C") (pintype "passive"))
      (node (ref "LED10") (pin "C") (pinfunction "C_C") (pintype "passive"))
      (node (ref "LED11") (pin "C") (pinfunction "C_C") (pintype "passive"))
      (node (ref "LED12") (pin "C") (pinfunction "C_C") (pintype "passive"))
      (node (ref "LED13") (pin "C") (pinfunction "C_C") (pintype "passive"))
      (node (ref "LED14") (pin "C") (pinfunction "C_C") (pintype "passive"))
      (node (ref "LED15") (pin "C") (pinfunction "C_C") (pintype "passive"))
      (node (ref "LED2") (pin "C") (pinfunction "C_C") (pintype "passive"))
      (node (ref "LED3") (pin "C") (pinfunction "C_C") (pintype "passive"))
      (node (ref "LED4") (pin "C") (pinfunction "C_C") (pintype "passive"))
      (node (ref "LED5") (pin "C") (pinfunction "C_C") (pintype "passive"))
      (node (ref "LED6") (pin "C") (pinfunction "C_C") (pintype "passive"))
      (node (ref "LED7") (pin "C") (pinfunction "C_C") (pintype "passive"))
      (node (ref "LED8") (pin "C") (pinfunction "C_C") (pintype "passive"))
      (node (ref "LED9") (pin "C") (pinfunction "C_C") (pintype "passive"))
      (node (ref "R18") (pin "1") (pinfunction "CCW_1") (pintype "passive"))
      (node (ref "SW1") (pin "1") (pinfunction "1_1") (pintype "bidirectional"))
      (node (ref "SW10") (pin "1") (pinfunction "1_1") (pintype "bidirectional"))
      (node (ref "SW11") (pin "1") (pinfunction "1_1") (pintype "bidirectional"))
      (node (ref "SW12") (pin "1") (pinfunction "1_1") (pintype "bidirectional"))
      (node (ref "SW13") (pin "1") (pinfunction "1_1") (pintype "bidirectional"))
      (node (ref "SW2") (pin "1") (pinfunction "1_1") (pintype "bidirectional"))
      (node (ref "SW3") (pin "1") (pinfunction "1_1") (pintype "bidirectional"))
      (node (ref "SW4") (pin "1") (pinfunction "1_1") (pintype "bidirectional"))
      (node (ref "SW5") (pin "1") (pinfunction "1_1") (pintype "bidirectional"))
      (node (ref "SW6") (pin "1") (pinfunction "1_1") (pintype "bidirectional"))
      (node (ref "SW7") (pin "1") (pinfunction "1_1") (pintype "bidirectional"))
      (node (ref "SW8") (pin "1") (pinfunction "1_1") (pintype "bidirectional"))
      (node (ref "SW9") (pin "1") (pinfunction "1_1") (pintype "bidirectional"))
      (node (ref "T1") (pin "E") (pinfunction "E_E") (pintype "passive"))
      (node (ref "T6") (pin "E") (pinfunction "E_E") (pintype "passive"))
      (node (ref "T7") (pin "E") (pinfunction "E_E") (pintype "passive"))
      (node (ref "T8") (pin "E") (pinfunction "E_E") (pintype "passive"))
      (node (ref "T9") (pin "E") (pinfunction "E_E") (pintype "passive"))
      (node (ref "TB1") (pin "1") (pinfunction "KL_1") (pintype "passive"))
      (node (ref "U$1") (pin "4") (pinfunction "GND_4") (pintype "power_in"))
      (node (ref "U$2") (pin "1") (pinfunction "GND_1") (pintype "input"))
      (node (ref "U$3") (pin "1") (pinfunction "GND_1") (pintype "input"))
    )
    (net (code "7") (name "I2C1_SCL") (class "Default")
      (node (ref "IC1") (pin "PB_6") (pinfunction "PB_6_PB_6") (pintype "bidirectional"))
      (node (ref "IC9") (pin "16") (pinfunction "SCL_16") (pintype "bidirectional"))
      (node (ref "R20") (pin "1") (pinfunction "1_1") (pintype "passive"))
    )
    (net (code "8") (name "I2C1_SDA") (class "Default")
      (node (ref "IC1") (pin "PB_7") (pinfunction "PB_7_PB_7") (pintype "bidirectional"))
      (node (ref "IC9") (pin "15") (pinfunction "SDA_15") (pintype "bidirectional"))
      (node (ref "R21") (pin "1") (pinfunction "1_1") (pintype "passive"))
    )
    (net (code "9") (name "LED_POWER") (class "Default")
      (node (ref "IC1") (pin "PB_0") (pinfunction "PB_0_PB_0") (pintype "bidirectional"))
      (node (ref "R16") (pin "1") (pinfunction "1_1") (pintype "passive"))
    )
    (net (code "10") (name "MODE_AUTO") (class "Default")
      (node (ref "IC5") (pin "15") (pinfunction "QA_15") (pintype "tri_state"))
      (node (ref "R1") (pin "1") (pinfunction "1_1") (pintype "passive"))
    )
    (net (code "11") (name "MODE_COOL") (class "Default")
      (node (ref "IC5") (pin "1") (pinfunction "QB_1") (pintype "tri_state"))
      (node (ref "R3") (pin "1") (pinfunction "1_1") (pintype "passive"))
    )
    (net (code "12") (name "MODE_DRY") (class "Default")
      (node (ref "IC5") (pin "2") (pinfunction "QC_2") (pintype "tri_state"))
      (node (ref "R5") (pin "1") (pinfunction "1_1") (pintype "passive"))
    )
    (net (code "13") (name "MODE_HEAT") (class "Default")
      (node (ref "IC5") (pin "3") (pinfunction "QD_3") (pintype "tri_state"))
      (node (ref "R4") (pin "1") (pinfunction "1_1") (pintype "passive"))
    )
    (net (code "14") (name "Net-(D3-PadC)") (class "Default")
      (node (ref "D3") (pin "C") (pinfunction "C_C") (pintype "passive"))
      (node (ref "SW9") (pin "2") (pinfunction "2_2") (pintype "bidirectional"))
    )
    (net (code "15") (name "Net-(DS2-A)") (class "Default")
      (node (ref "DS2") (pin "11") (pinfunction "A_11") (pintype "input"))
      (node (ref "R29") (pin "2") (pinfunction "2_2") (pintype "passive"))
    )
    (net (code "16") (name "Net-(DS2-B)") (class "Default")
      (node (ref "DS2") (pin "7") (pinfunction "B_7") (pintype "input"))
      (node (ref "R30") (pin "2") (pinfunction "2_2") (pintype "passive"))
    )
    (net (code "17") (name "Net-(DS2-C)") (class "Default")
      (node (ref "DS2") (pin "4") (pinfunction "C_4") (pintype "input"))
      (node (ref "R31") (pin "2") (pinfunction "2_2") (pintype "passive"))
    )
    (net (code "18") (name "Net-(DS2-D)") (class "Default")
      (node (ref "DS2") (pin "2") (pinfunction "D_2") (pintype "input"))
      (node (ref "R32") (pin "2") (pinfunction "2_2") (pintype "passive"))
    )
    (net (code "19") (name "Net-(DS2-DIG1)") (class "Default")
      (node (ref "DS2") (pin "12") (pinfunction "DIG1_12") (pintype "input"))
      (node (ref "T2") (pin "E") (pinfunction "E_E") (pintype "passive"))
    )
    (net (code "20") (name "Net-(DS2-DIG2)") (class "Default")
      (node (ref "DS2") (pin "9") (pinfunction "DIG2_9") (pintype "input"))
      (node (ref "T3") (pin "E") (pinfunction "E_E") (pintype "passive"))
    )
    (net (code "21") (name "Net-(DS2-DIG3)") (class "Default")
      (node (ref "DS2") (pin "8") (pinfunction "DIG3_8") (pintype "input"))
      (node (ref "T4") (pin "E") (pinfunction "E_E") (pintype "passive"))
    )
    (net (code "22") (name "Net-(DS2-DIG4)") (class "Default")
      (node (ref "DS2") (pin "6") (pinfunction "DIG4_6") (pintype "input"))
      (node (ref "T5") (pin "E") (pinfunction "E_E") (pintype "passive"))
    )
    (net (code "23") (name "Net-(DS2-E)") (class "Default")
      (node (ref "DS2") (pin "1") (pinfunction "E_1") (pintype "input"))
      (node (ref "R33") (pin "2") (pinfunction "2_2") (pintype "passive"))
    )
    (net (code "24") (name "Net-(DS2-F)") (class "Default")
      (node (ref "DS2") (pin "10") (pinfunction "F_10") (pintype "input"))
      (node (ref "R34") (pin "2") (pinfunction "2_2") (pintype "passive"))
    )
    (net (code "25") (name "Net-(DS2-G)") (class "Default")
      (node (ref "DS2") (pin "5") (pinfunction "G_5") (pintype "input"))
      (node (ref "R35") (pin "2") (pinfunction "2_2") (pintype "passive"))
    )
    (net (code "26") (name "Net-(DS2-H)") (class "Default")
      (node (ref "DS2") (pin "3") (pinfunction "H_3") (pintype "input"))
      (node (ref "R36") (pin "2") (pinfunction "2_2") (pintype "passive"))
    )
    (net (code "27") (name "Net-(IC2A-I0)") (class "Default")
      (node (ref "D2") (pin "C") (pinfunction "C_C") (pintype "passive"))
      (node (ref "IC2") (pin "1") (pinfunction "I0_1") (pintype "input"))
      (node (ref "RN3") (pin "4") (pinfunction "1_4") (pintype "passive"))
      (node (ref "SW10") (pin "2") (pinfunction "2_2") (pintype "bidirectional"))
    )
    (net (code "28") (name "Net-(IC2A-I1)") (class "Default")
      (node (ref "IC2") (pin "2") (pinfunction "I1_2") (pintype "input"))
      (node (ref "IC3") (pin "9") (pinfunction "A0_9") (pintype "output"))
    )
    (net (code "29") (name "Net-(IC2B-I0)") (class "Default")
      (node (ref "IC2") (pin "4") (pinfunction "I0_4") (pintype "input"))
      (node (ref "IC3") (pin "7") (pinfunction "A1_7") (pintype "output"))
    )
    (net (code "30") (name "Net-(IC2B-I1)") (class "Default")
      (node (ref "D1") (pin "C") (pinfunction "C_C") (pintype "passive"))
      (node (ref "IC2") (pin "5") (pinfunction "I1_5") (pintype "input"))
      (node (ref "RN3") (pin "3") (pinfunction "1_3") (pintype "passive"))
      (node (ref "SW11") (pin "2") (pinfunction "2_2") (pintype "bidirectional"))
    )
    (net (code "31") (name "Net-(IC2C-I0)") (class "Default")
      (node (ref "D1") (pin "A") (pinfunction "A_A") (pintype "passive"))
      (node (ref "D2") (pin "A") (pinfunction "A_A") (pintype "passive"))
      (node (ref "D3") (pin "A") (pinfunction "A_A") (pintype "passive"))
      (node (ref "IC2") (pin "10") (pinfunction "I1_10") (pintype "input"))
      (node (ref "IC2") (pin "12") (pinfunction "I0_12") (pintype "input"))
      (node (ref "IC2") (pin "9") (pinfunction "I0_9") (pintype "input"))
      (node (ref "RN3") (pin "2") (pinfunction "1_2") (pintype "passive"))
    )
    (net (code "32") (name "Net-(IC2D-I1)") (class "Default")
      (node (ref "IC2") (pin "13") (pinfunction "I1_13") (pintype "input"))
      (node (ref "IC3") (pin "14") (pinfunction "GS_14") (pintype "output"))
    )
    (net (code "33") (name "Net-(IC3A-0)") (class "Default")
      (node (ref "IC3") (pin "10") (pinfunction "0_10") (pintype "input"))
      (node (ref "RN1") (pin "3") (pinfunction "1_3") (pintype "passive"))
      (node (ref "SW1") (pin "2") (pinfunction "2_2") (pintype "bidirectional"))
    )
    (net (code "34") (name "Net-(IC3A-1)") (class "Default")
      (node (ref "IC3") (pin "11") (pinfunction "1_11") (pintype "input"))
      (node (ref "RN1") (pin "4") (pinfunction "1_4") (pintype "passive"))
      (node (ref "SW2") (pin "2") (pinfunction "2_2") (pintype "bidirectional"))
    )
    (net (code "35") (name "Net-(IC3A-2)") (class "Default")
      (node (ref "IC3") (pin "12") (pinfunction "2_12") (pintype "input"))
      (node (ref "RN1") (pin "2") (pinfunction "1_2") (pintype "passive"))
      (node (ref "SW3") (pin "2") (pinfunction "2_2") (pintype "bidirectional"))
    )
    (net (code "36") (name "Net-(IC3A-3)") (class "Default")
      (node (ref "IC3") (pin "13") (pinfunction "3_13") (pintype "input"))
      (node (ref "RN1") (pin "1") (pinfunction "1_1") (pintype "passive"))
      (node (ref "SW4") (pin "2") (pinfunction "2_2") (pintype "bidirectional"))
    )
    (net (code "37") (name "Net-(IC3A-4)") (class "Default")
      (node (ref "IC3") (pin "1") (pinfunction "4_1") (pintype "input"))
      (node (ref "RN2") (pin "4") (pinfunction "1_4") (pintype "passive"))
      (node (ref "SW5") (pin "2") (pinfunction "2_2") (pintype "bidirectional"))
    )
    (net (code "38") (name "Net-(IC3A-5)") (class "Default")
      (node (ref "IC3") (pin "2") (pinfunction "5_2") (pintype "input"))
      (node (ref "RN2") (pin "3") (pinfunction "1_3") (pintype "passive"))
      (node (ref "SW6") (pin "2") (pinfunction "2_2") (pintype "bidirectional"))
    )
    (net (code "39") (name "Net-(IC3A-6)") (class "Default")
      (node (ref "IC3") (pin "3") (pinfunction "6_3") (pintype "input"))
      (node (ref "RN2") (pin "2") (pinfunction "1_2") (pintype "passive"))
      (node (ref "SW7") (pin "2") (pinfunction "2_2") (pintype "bidirectional"))
    )
    (net (code "40") (name "Net-(IC3A-7)") (class "Default")
      (node (ref "IC3") (pin "4") (pinfunction "7_4") (pintype "input"))
      (node (ref "RN2") (pin "1") (pinfunction "1_1") (pintype "passive"))
      (node (ref "SW8") (pin "2") (pinfunction "2_2") (pintype "bidirectional"))
    )
    (net (code "41") (name "Net-(IC5A-QH*)") (class "Default")
      (node (ref "IC5") (pin "9") (pinfunction "QH*_9") (pintype "tri_state"))
      (node (ref "IC6") (pin "14") (pinfunction "SER_14") (pintype "input"))
    )
    (net (code "42") (name "Net-(IC9-VBAT)") (class "Default")
      (node (ref "B1") (pin "+") (pinfunction "+_+") (pintype "passive"))
      (node (ref "C12") (pin "1") (pinfunction "1_1") (pintype "passive"))
      (node (ref "IC9") (pin "14") (pinfunction "VBAT_14") (pintype "power_in"))
    )
    (net (code "43") (name "Net-(K1A-2-)") (class "Default")
      (node (ref "D7") (pin "A") (pinfunction "A_A") (pintype "passive"))
      (node (ref "K1") (pin "12") (pinfunction "2-_12") (pintype "passive"))
      (node (ref "LED16") (pin "C") (pinfunction "C_C") (pintype "passive"))
      (node (ref "T7") (pin "C") (pinfunction "C_C") (pintype "passive"))
    )
    (net (code "44") (name "Net-(K1B-P)") (class "Default")
      (node (ref "K1") (pin "4") (pinfunction "P_4") (pintype "passive"))
      (node (ref "TB3") (pin "1") (pinfunction "KL_1") (pintype "passive"))
    )
    (net (code "45") (name "Net-(K1B-S)") (class "Default")
      (node (ref "K1") (pin "3") (pinfunction "S_3") (pintype "passive"))
      (node (ref "TB3") (pin "2") (pinfunction "KL_2") (pintype "passive"))
    )
    (net (code "46") (name "Net-(K2A-2-)") (class "Default")
      (node (ref "D9") (pin "A") (pinfunction "A_A") (pintype "passive"))
      (node (ref "K2") (pin "12") (pinfunction "2-_12") (pintype "passive"))
      (node (ref "LED18") (pin "C") (pinfunction "C_C") (pintype "passive"))
      (node (ref "T9") (pin "C") (pinfunction "C_C") (pintype "passive"))
    )
    (net (code "47") (name "Net-(K2B-P)") (class "Default")
      (node (ref "K2") (pin "4") (pinfunction "P_4") (pintype "passive"))
      (node (ref "TB2") (pin "1") (pinfunction "KL_1") (pintype "passive"))
    )
    (net (code "48") (name "Net-(K2B-S)") (class "Default")
      (node (ref "K2") (pin "3") (pinfunction "S_3") (pintype "passive"))
      (node (ref "TB2") (pin "2") (pinfunction "KL_2") (pintype "passive"))
    )
    (net (code "49") (name "Net-(K3A-2-)") (class "Default")
      (node (ref "D8") (pin "A") (pinfunction "A_A") (pintype "passive"))
      (node (ref "K3") (pin "12") (pinfunction "2-_12") (pintype "passive"))
      (node (ref "LED17") (pin "C") (pinfunction "C_C") (pintype "passive"))
      (node (ref "T8") (pin "C") (pinfunction "C_C") (pintype "passive"))
    )
    (net (code "50") (name "Net-(K3B-P)") (class "Default")
      (node (ref "K3") (pin "4") (pinfunction "P_4") (pintype "passive"))
      (node (ref "TB4") (pin "1") (pinfunction "KL_1") (pintype "passive"))
    )
    (net (code "51") (name "Net-(K3B-S)") (class "Default")
      (node (ref "K3") (pin "3") (pinfunction "S_3") (pintype "passive"))
      (node (ref "TB4") (pin "2") (pinfunction "KL_2") (pintype "passive"))
    )
    (net (code "52") (name "Net-(LED1-PadA)") (class "Default")
      (node (ref "LED1") (pin "A") (pinfunction "A_A") (pintype "passive"))
      (node (ref "R1") (pin "2") (pinfunction "2_2") (pintype "passive"))
    )
    (net (code "53") (name "Net-(LED2-PadA)") (class "Default")
      (node (ref "LED2") (pin "A") (pinfunction "A_A") (pintype "passive"))
      (node (ref "R3") (pin "2") (pinfunction "2_2") (pintype "passive"))
    )
    (net (code "54") (name "Net-(LED3-PadA)") (class "Default")
      (node (ref "LED3") (pin "A") (pinfunction "A_A") (pintype "passive"))
      (node (ref "R4") (pin "2") (pinfunction "2_2") (pintype "passive"))
    )
    (net (code "55") (name "Net-(LED4-PadA)") (class "Default")
      (node (ref "LED4") (pin "A") (pinfunction "A_A") (pintype "passive"))
      (node (ref "R5") (pin "2") (pinfunction "2_2") (pintype "passive"))
    )
    (net (code "56") (name "Net-(LED5-PadA)") (class "Default")
      (node (ref "LED5") (pin "A") (pinfunction "A_A") (pintype "passive"))
      (node (ref "R6") (pin "2") (pinfunction "2_2") (pintype "passive"))
    )
    (net (code "57") (name "Net-(LED6-PadA)") (class "Default")
      (node (ref "LED6") (pin "A") (pinfunction "A_A") (pintype "passive"))
      (node (ref "R7") (pin "2") (pinfunction "2_2") (pintype "passive"))
    )
    (net (code "58") (name "Net-(LED7-PadA)") (class "Default")
      (node (ref "LED7") (pin "A") (pinfunction "A_A") (pintype "passive"))
      (node (ref "R9") (pin "2") (pinfunction "2_2") (pintype "passive"))
    )
    (net (code "59") (name "Net-(LED8-PadA)") (class "Default")
      (node (ref "LED8") (pin "A") (pinfunction "A_A") (pintype "passive"))
      (node (ref "R8") (pin "2") (pinfunction "2_2") (pintype "passive"))
    )
    (net (code "60") (name "Net-(LED9-PadA)") (class "Default")
      (node (ref "LED9") (pin "A") (pinfunction "A_A") (pintype "passive"))
      (node (ref "R10") (pin "2") (pinfunction "2_2") (pintype "passive"))
    )
    (net (code "61") (name "Net-(LED10-PadA)") (class "Default")
      (node (ref "LED10") (pin "A") (pinfunction "A_A") (pintype "passive"))
      (node (ref "R11") (pin "2") (pinfunction "2_2") (pintype "passive"))
    )
    (net (code "62") (name "Net-(LED11-PadA)") (class "Default")
      (node (ref "LED11") (pin "A") (pinfunction "A_A") (pintype "passive"))
      (node (ref "R13") (pin "2") (pinfunction "2_2") (pintype "passive"))
    )
    (net (code "63") (name "Net-(LED12-PadA)") (class "Default")
      (node (ref "LED12") (pin "A") (pinfunction "A_A") (pintype "passive"))
      (node (ref "R12") (pin "2") (pinfunction "2_2") (pintype "passive"))
    )
    (net (code "64") (name "Net-(LED13-PadA)") (class "Default")
      (node (ref "LED13") (pin "A") (pinfunction "A_A") (pintype "passive"))
      (node (ref "R14") (pin "2") (pinfunction "2_2") (pintype "passive"))
    )
    (net (code "65") (name "Net-(LED14-PadA)") (class "Default")
      (node (ref "LED14") (pin "A") (pinfunction "A_A") (pintype "passive"))
      (node (ref "R15") (pin "2") (pinfunction "2_2") (pintype "passive"))
    )
    (net (code "66") (name "Net-(LED15-PadA)") (class "Default")
      (node (ref "LED15") (pin "A") (pinfunction "A_A") (pintype "passive"))
      (node (ref "R16") (pin "2") (pinfunction "2_2") (pintype "passive"))
    )
    (net (code "67") (name "Net-(LED16-PadA)") (class "Default")
      (node (ref "LED16") (pin "A") (pinfunction "A_A") (pintype "passive"))
      (node (ref "R26") (pin "2") (pinfunction "2_2") (pintype "passive"))
    )
    (net (code "68") (name "Net-(LED17-PadA)") (class "Default")
      (node (ref "LED17") (pin "A") (pinfunction "A_A") (pintype "passive"))
      (node (ref "R25") (pin "2") (pinfunction "2_2") (pintype "passive"))
    )
    (net (code "69") (name "Net-(LED18-PadA)") (class "Default")
      (node (ref "LED18") (pin "A") (pinfunction "A_A") (pintype "passive"))
      (node (ref "R28") (pin "2") (pinfunction "2_2") (pintype "passive"))
    )
    (net (code "70") (name "Net-(LS1-2)") (class "Default")
      (node (ref "D6") (pin "A") (pinfunction "A_A") (pintype "passive"))
      (node (ref "LS1") (pin "-") (pinfunction "2_-") (pintype "passive"))
      (node (ref "T6") (pin "C") (pinfunction "C_C") (pintype "passive"))
    )
    (net (code "71") (name "Net-(Q2-G)") (class "Default")
      (node (ref "D5") (pin "C") (pinfunction "C_C") (pintype "passive"))
      (node (ref "Q2") (pin "1") (pinfunction "G_1") (pintype "passive"))
      (node (ref "Q3") (pin "1") (pinfunction "G_1") (pintype "passive"))
      (node (ref "R23") (pin "2") (pinfunction "2_2") (pintype "passive"))
    )
    (net (code "72") (name "Net-(R2-Pad1)") (class "Default")
      (node (ref "R2") (pin "1") (pinfunction "1_1") (pintype "passive"))
      (node (ref "T1") (pin "B") (pinfunction "B_B") (pintype "passive"))
    )
    (net (code "73") (name "Net-(R19-Pad2)") (class "Default")
      (node (ref "R19") (pin "2") (pinfunction "2_2") (pintype "passive"))
      (node (ref "T6") (pin "B") (pinfunction "B_B") (pintype "passive"))
    )
    (net (code "74") (name "Net-(R22-Pad2)") (class "Default")
      (node (ref "R22") (pin "2") (pinfunction "2_2") (pintype "passive"))
      (node (ref "T7") (pin "B") (pinfunction "B_B") (pintype "passive"))
    )
    (net (code "75") (name "Net-(R24-Pad2)") (class "Default")
      (node (ref "R24") (pin "2") (pinfunction "2_2") (pintype "passive"))
      (node (ref "T8") (pin "B") (pinfunction "B_B") (pintype "passive"))
    )
    (net (code "76") (name "Net-(R27-Pad2)") (class "Default")
      (node (ref "R27") (pin "2") (pinfunction "2_2") (pintype "passive"))
      (node (ref "T9") (pin "B") (pinfunction "B_B") (pintype "passive"))
    )
    (net (code "77") (name "Net-(RN6-Pad1)") (class "Default")
      (node (ref "RN6") (pin "1") (pinfunction "1_1") (pintype "passive"))
      (node (ref "T5") (pin "B") (pinfunction "B_B") (pintype "passive"))
    )
    (net (code "78") (name "Net-(RN6B-1)") (class "Default")
      (node (ref "RN6") (pin "2") (pinfunction "1_2") (pintype "passive"))
      (node (ref "T4") (pin "B") (pinfunction "B_B") (pintype "passive"))
    )
    (net (code "79") (name "Net-(RN6C-1)") (class "Default")
      (node (ref "RN6") (pin "3") (pinfunction "1_3") (pintype "passive"))
      (node (ref "T3") (pin "B") (pinfunction "B_B") (pintype "passive"))
    )
    (net (code "80") (name "Net-(RN6D-1)") (class "Default")
      (node (ref "RN6") (pin "4") (pinfunction "1_4") (pintype "passive"))
      (node (ref "T2") (pin "B") (pinfunction "B_B") (pintype "passive"))
    )
    (net (code "81") (name "Net-(TB1B-KL)") (class "Default")
      (node (ref "D4") (pin "A") (pinfunction "A_A") (pintype "passive"))
      (node (ref "TB1") (pin "2") (pinfunction "KL_2") (pintype "passive"))
    )
    (net (code "82") (name "OUT_CLOCK") (class "Default")
      (node (ref "IC1") (pin "PB_10") (pinfunction "PB_10_PB_10") (pintype "bidirectional"))
      (node (ref "IC5") (pin "11") (pinfunction "SCK_11") (pintype "input"))
      (node (ref "IC6") (pin "11") (pinfunction "SCK_11") (pintype "input"))
    )
    (net (code "83") (name "OUT_DATA") (class "Default")
      (node (ref "IC1") (pin "PB_12") (pinfunction "PB_12_PB_12") (pintype "bidirectional"))
      (node (ref "IC5") (pin "14") (pinfunction "SER_14") (pintype "input"))
    )
    (net (code "84") (name "OUT_LATCH") (class "Default")
      (node (ref "IC1") (pin "PB_11") (pinfunction "PB_11_PB_11") (pintype "bidirectional"))
      (node (ref "IC5") (pin "12") (pinfunction "RCK_12") (pintype "input"))
      (node (ref "IC6") (pin "12") (pinfunction "RCK_12") (pintype "input"))
    )
    (net (code "85") (name "PIN_1") (class "Default")
      (node (ref "J1") (pin "1") (pinfunction "1_1") (pintype "passive"))
    )
    (net (code "86") (name "PIN_2") (class "Default")
      (node (ref "J1") (pin "2") (pinfunction "2_2") (pintype "passive"))
      (node (ref "JP4") (pin "2") (pinfunction "2_2") (pintype "passive"))
      (node (ref "JP8") (pin "2") (pinfunction "2_2") (pintype "passive"))
    )
    (net (code "87") (name "PIN_3") (class "Default")
      (node (ref "J1") (pin "3") (pinfunction "3_3") (pintype "passive"))
      (node (ref "JP10") (pin "2") (pinfunction "2_2") (pintype "passive"))
    )
    (net (code "88") (name "PIN_4") (class "Default")
      (node (ref "J1") (pin "4") (pinfunction "4_4") (pintype "passive"))
      (node (ref "JP3") (pin "2") (pinfunction "2_2") (pintype "passive"))
    )
    (net (code "89") (name "PIN_5") (class "Default")
      (node (ref "J1") (pin "5") (pinfunction "5_5") (pintype "passive"))
      (node (ref "JP5") (pin "2") (pinfunction "2_2") (pintype "passive"))
    )
    (net (code "90") (name "PIN_6") (class "Default")
      (node (ref "J1") (pin "6") (pinfunction "6_6") (pintype "passive"))
      (node (ref "JP9") (pin "2") (pinfunction "2_2") (pintype "passive"))
    )
    (net (code "91") (name "RELAY_COOL") (class "Default")
      (node (ref "IC1") (pin "PB_8") (pinfunction "PB_8_PB_8") (pintype "bidirectional"))
      (node (ref "R24") (pin "1") (pinfunction "1_1") (pintype "passive"))
    )
    (net (code "92") (name "RELAY_FAN") (class "Default")
      (node (ref "IC1") (pin "PA_12") (pinfunction "PA_12_PA_12") (pintype "bidirectional"))
      (node (ref "R22") (pin "1") (pinfunction "1_1") (pintype "passive"))
    )
    (net (code "93") (name "RELAY_HEAT") (class "Default")
      (node (ref "IC1") (pin "PB_9") (pinfunction "PB_9_PB_9") (pintype "bidirectional"))
      (node (ref "R27") (pin "1") (pinfunction "1_1") (pintype "passive"))
    )
    (net (code "94") (name "SEG_A") (class "Default")
      (node (ref "IC4") (pin "7") (pinfunction "QH_7") (pintype "tri_state"))
      (node (ref "R29") (pin "1") (pinfunction "1_1") (pintype "passive"))
    )
    (net (code "95") (name "SEG_B") (class "Default")
      (node (ref "IC4") (pin "6") (pinfunction "QG_6") (pintype "tri_state"))
      (node (ref "R30") (pin "1") (pinfunction "1_1") (pintype "passive"))
    )
    (net (code "96") (name "SEG_C") (class "Default")
      (node (ref "IC4") (pin "5") (pinfunction "QF_5") (pintype "tri_state"))
      (node (ref "R31") (pin "1") (pinfunction "1_1") (pintype "passive"))
    )
    (net (code "97") (name "SEG_CLOCK") (class "Default")
      (node (ref "IC1") (pin "PB_14") (pinfunction "PB_14_PB_14") (pintype "bidirectional"))
      (node (ref "IC4") (pin "11") (pinfunction "SCK_11") (pintype "input"))
    )
    (net (code "98") (name "SEG_D") (class "Default")
      (node (ref "IC4") (pin "4") (pinfunction "QE_4") (pintype "tri_state"))
      (node (ref "R32") (pin "1") (pinfunction "1_1") (pintype "passive"))
    )
    (net (code "99") (name "SEG_DATA") (class "Default")
      (node (ref "IC1") (pin "PB_13") (pinfunction "PB_13_PB_13") (pintype "bidirectional"))
      (node (ref "IC4") (pin "14") (pinfunction "SER_14") (pintype "input"))
    )
    (net (code "100") (name "SEG_DIG1") (class "Default")
      (node (ref "IC1") (pin "PA_15") (pinfunction "PA_15_PA_15") (pintype "bidirectional"))
      (node (ref "RN6") (pin "5") (pinfunction "2_5") (pintype "passive"))
    )
    (net (code "101") (name "SEG_DIG2") (class "Default")
      (node (ref "IC1") (pin "PB_3") (pinfunction "PB_3_PB_3") (pintype "bidirectional"))
      (node (ref "RN6") (pin "6") (pinfunction "2_6") (pintype "passive"))
    )
    (net (code "102") (name "SEG_DIG3") (class "Default")
      (node (ref "IC1") (pin "PB_4") (pinfunction "PB_4_PB_4") (pintype "bidirectional"))
      (node (ref "RN6") (pin "7") (pinfunction "2_7") (pintype "passive"))
    )
    (net (code "103") (name "SEG_DIG4") (class "Default")
      (node (ref "IC1") (pin "PB_5") (pinfunction "PB_5_PB_5") (pintype "bidirectional"))
      (node (ref "RN6") (pin "8") (pinfunction "2_8") (pintype "passive"))
    )
    (net (code "104") (name "SEG_DP") (class "Default")
      (node (ref "IC4") (pin "15") (pinfunction "QA_15") (pintype "tri_state"))
      (node (ref "R36") (pin "1") (pinfunction "1_1") (pintype "passive"))
    )
    (net (code "105") (name "SEG_E") (class "Default")
      (node (ref "IC4") (pin "3") (pinfunction "QD_3") (pintype "tri_state"))
      (node (ref "R33") (pin "1") (pinfunction "1_1") (pintype "passive"))
    )
    (net (code "106") (name "SEG_F") (class "Default")
      (node (ref "IC4") (pin "2") (pinfunction "QC_2") (pintype "tri_state"))
      (node (ref "R34") (pin "1") (pinfunction "1_1") (pintype "passive"))
    )
    (net (code "107") (name "SEG_G") (class "Default")
      (node (ref "IC4") (pin "1") (pinfunction "QB_1") (pintype "tri_state"))
      (node (ref "R35") (pin "1") (pinfunction "1_1") (pintype "passive"))
    )
    (net (code "108") (name "SEG_LATCH") (class "Default")
      (node (ref "IC1") (pin "PB_15") (pinfunction "PB_15_PB_15") (pintype "bidirectional"))
      (node (ref "IC4") (pin "12") (pinfunction "RCK_12") (pintype "input"))
    )
    (net (code "109") (name "SPEED_AUTO") (class "Default")
      (node (ref "IC6") (pin "15") (pinfunction "QA_15") (pintype "tri_state"))
      (node (ref "R12") (pin "1") (pinfunction "1_1") (pintype "passive"))
    )
    (net (code "110") (name "SPEED_HIGH") (class "Default")
      (node (ref "IC6") (pin "3") (pinfunction "QD_3") (pintype "tri_state"))
      (node (ref "R14") (pin "1") (pinfunction "1_1") (pintype "passive"))
    )
    (net (code "111") (name "SPEED_LOW") (class "Default")
      (node (ref "IC6") (pin "1") (pinfunction "QB_1") (pintype "tri_state"))
      (node (ref "R13") (pin "1") (pinfunction "1_1") (pintype "passive"))
    )
    (net (code "112") (name "SPEED_MID") (class "Default")
      (node (ref "IC6") (pin "2") (pinfunction "QC_2") (pintype "tri_state"))
      (node (ref "R15") (pin "1") (pinfunction "1_1") (pintype "passive"))
    )
    (net (code "113") (name "STLINK_3V3") (class "Default")
      (node (ref "J1") (pin "7") (pinfunction "7_7") (pintype "passive"))
      (node (ref "J1") (pin "8") (pinfunction "8_8") (pintype "passive"))
      (node (ref "Q2") (pin "3") (pinfunction "D_3") (pintype "passive"))
    )
    (net (code "114") (name "STLINK_5V") (class "Default")
      (node (ref "J1") (pin "10") (pinfunction "10_10") (pintype "passive"))
      (node (ref "J1") (pin "9") (pinfunction "9_9") (pintype "passive"))
      (node (ref "Q3") (pin "3") (pinfunction "D_3") (pintype "passive"))
    )
    (net (code "115") (name "SWCLK") (class "Default")
      (node (ref "IC1") (pin "SWCLK") (pinfunction "SWCLK_SWCLK") (pintype "bidirectional"))
      (node (ref "IC1") (pin "SWCLK1") (pinfunction "SWCLK_SWCLK1") (pintype "bidirectional"))
      (node (ref "JP4") (pin "1") (pinfunction "1_1") (pintype "passive"))
      (node (ref "JP9") (pin "1") (pinfunction "1_1") (pintype "passive"))
    )
    (net (code "116") (name "SWDIO") (class "Default")
      (node (ref "IC1") (pin "SWDIO") (pinfunction "SWDIO_SWDIO") (pintype "bidirectional"))
      (node (ref "IC1") (pin "SWDIO1") (pinfunction "SWDIO_SWDIO1") (pintype "bidirectional"))
      (node (ref "JP3") (pin "1") (pinfunction "1_1") (pintype "passive"))
      (node (ref "JP8") (pin "1") (pinfunction "1_1") (pintype "passive"))
    )
    (net (code "117") (name "SWING_AUTO") (class "Default")
      (node (ref "IC5") (pin "4") (pinfunction "QE_4") (pintype "tri_state"))
      (node (ref "R8") (pin "1") (pinfunction "1_1") (pintype "passive"))
    )
    (net (code "118") (name "SWING_DOWN") (class "Default")
      (node (ref "IC5") (pin "5") (pinfunction "QF_5") (pintype "tri_state"))
      (node (ref "R9") (pin "1") (pinfunction "1_1") (pintype "passive"))
    )
    (net (code "119") (name "SWING_MID") (class "Default")
      (node (ref "IC5") (pin "6") (pinfunction "QG_6") (pintype "tri_state"))
      (node (ref "R11") (pin "1") (pinfunction "1_1") (pintype "passive"))
    )
    (net (code "120") (name "SWING_TOP") (class "Default")
      (node (ref "IC5") (pin "7") (pinfunction "QH_7") (pintype "tri_state"))
      (node (ref "R10") (pin "1") (pinfunction "1_1") (pintype "passive"))
    )
    (net (code "121") (name "SW_B0") (class "Default")
      (node (ref "IC1") (pin "PA_1") (pinfunction "PA_1_PA_1") (pintype "bidirectional"))
      (node (ref "IC2") (pin "3") (pinfunction "O_3") (pintype "output"))
    )
    (net (code "122") (name "SW_B1") (class "Default")
      (node (ref "IC1") (pin "PA_2") (pinfunction "PA_2_PA_2") (pintype "bidirectional"))
      (node (ref "IC2") (pin "6") (pinfunction "O_6") (pintype "output"))
    )
    (net (code "123") (name "SW_B2") (class "Default")
      (node (ref "IC1") (pin "PA_3") (pinfunction "PA_3_PA_3") (pintype "bidirectional"))
      (node (ref "IC3") (pin "6") (pinfunction "A2_6") (pintype "output"))
    )
    (net (code "124") (name "SW_B3") (class "Default")
      (node (ref "IC1") (pin "PA_4") (pinfunction "PA_4_PA_4") (pintype "bidirectional"))
      (node (ref "IC2") (pin "8") (pinfunction "O_8") (pintype "output"))
      (node (ref "R2") (pin "2") (pinfunction "2_2") (pintype "passive"))
    )
    (net (code "125") (name "SW_EN") (class "Default")
      (node (ref "IC3") (pin "5") (pinfunction "EI_5") (pintype "input"))
      (node (ref "RN3") (pin "1") (pinfunction "1_1") (pintype "passive"))
      (node (ref "T1") (pin "C") (pinfunction "C_C") (pintype "passive"))
    )
    (net (code "126") (name "SW_GS") (class "Default")
      (node (ref "IC1") (pin "PA_5") (pinfunction "PA_5_PA_5") (pintype "bidirectional"))
      (node (ref "IC2") (pin "11") (pinfunction "O_11") (pintype "output"))
    )
    (net (code "127") (name "SW_POWER") (class "Default")
      (node (ref "IC1") (pin "PA_6") (pinfunction "PA_6_PA_6") (pintype "bidirectional"))
      (node (ref "SW12") (pin "2") (pinfunction "2_2") (pintype "bidirectional"))
    )
    (net (code "128") (name "TIMER_OFF") (class "Default")
      (node (ref "IC6") (pin "5") (pinfunction "QF_5") (pintype "tri_state"))
      (node (ref "R6") (pin "1") (pinfunction "1_1") (pintype "passive"))
    )
    (net (code "129") (name "TIMER_ON") (class "Default")
      (node (ref "IC6") (pin "4") (pinfunction "QE_4") (pintype "tri_state"))
      (node (ref "R7") (pin "1") (pinfunction "1_1") (pintype "passive"))
    )
    (net (code "130") (name "VIN") (class "Default")
      (node (ref "C11") (pin "1") (pinfunction "1_1") (pintype "passive"))
      (node (ref "D4") (pin "C") (pinfunction "C_C") (pintype "passive"))
      (node (ref "R23") (pin "1") (pinfunction "1_1") (pintype "passive"))
      (node (ref "U$2") (pin "3") (pinfunction "IN_3") (pintype "input"))
      (node (ref "U$3") (pin "3") (pinfunction "IN_3") (pintype "input"))
    )
    (net (code "131") (name "unconnected-(IC1-3.3V-Pad3.3V_2)") (class "Default")
      (node (ref "IC1") (pin "3.3V_2") (pinfunction "3.3V_3.3V_2") (pintype "bidirectional"))
    )
    (net (code "132") (name "unconnected-(IC1-GND-PadGND_1)") (class "Default")
      (node (ref "IC1") (pin "GND_1") (pinfunction "GND_GND_1") (pintype "bidirectional"))
    )
    (net (code "133") (name "unconnected-(IC1-PadPA_8)") (class "Default")
      (node (ref "IC1") (pin "PA_8") (pinfunction "PA_8_PA_8") (pintype "bidirectional"))
    )
    (net (code "134") (name "unconnected-(IC1-PadPA_9)") (class "Default")
      (node (ref "IC1") (pin "PA_9") (pinfunction "PA_9_PA_9") (pintype "bidirectional"))
    )
    (net (code "135") (name "unconnected-(IC1-PadPA_10)") (class "Default")
      (node (ref "IC1") (pin "PA_10") (pinfunction "PA_10_PA_10") (pintype "bidirectional"))
    )
    (net (code "136") (name "unconnected-(IC1-PadPA_11)") (class "Default")
      (node (ref "IC1") (pin "PA_11") (pinfunction "PA_11_PA_11") (pintype "bidirectional"))
    )
    (net (code "137") (name "unconnected-(IC1-PadPC_13)") (class "Default")
      (node (ref "IC1") (pin "PC_13") (pinfunction "PC_13_PC_13") (pintype "bidirectional"))
    )
    (net (code "138") (name "unconnected-(IC1-PadPC_14)") (class "Default")
      (node (ref "IC1") (pin "PC_14") (pinfunction "PC_14_PC_14") (pintype "bidirectional"))
    )
    (net (code "139") (name "unconnected-(IC1-PadPC_15)") (class "Default")
      (node (ref "IC1") (pin "PC_15") (pinfunction "PC_15_PC_15") (pintype "bidirectional"))
    )
    (net (code "140") (name "unconnected-(IC1-PadVB)") (class "Default")
      (node (ref "IC1") (pin "VB") (pinfunction "VB_VB") (pintype "bidirectional"))
    )
    (net (code "141") (name "unconnected-(IC3A-EO-Pad15)") (class "Default")
      (node (ref "IC3") (pin "15") (pinfunction "EO_15") (pintype "output"))
    )
    (net (code "142") (name "unconnected-(IC4A-QH*-Pad9)") (class "Default")
      (node (ref "IC4") (pin "9") (pinfunction "QH*_9") (pintype "tri_state"))
    )
    (net (code "143") (name "unconnected-(IC6A-QG-Pad6)") (class "Default")
      (node (ref "IC6") (pin "6") (pinfunction "QG_6") (pintype "tri_state"))
    )
    (net (code "144") (name "unconnected-(IC6A-QH*-Pad9)") (class "Default")
      (node (ref "IC6") (pin "9") (pinfunction "QH*_9") (pintype "tri_state"))
    )
    (net (code "145") (name "unconnected-(IC6A-QH-Pad7)") (class "Default")
      (node (ref "IC6") (pin "7") (pinfunction "QH_7") (pintype "tri_state"))
    )
    (net (code "146") (name "unconnected-(IC9-32KHZ-Pad1)") (class "Default")
      (node (ref "IC9") (pin "1") (pinfunction "32KHZ_1") (pintype "output"))
    )
    (net (code "147") (name "unconnected-(IC9-NC-Pad5)") (class "Default")
      (node (ref "IC9") (pin "5") (pinfunction "NC_5") (pintype "no_connect"))
    )
    (net (code "148") (name "unconnected-(IC9-NC1-Pad6)") (class "Default")
      (node (ref "IC9") (pin "6") (pinfunction "NC1_6") (pintype "no_connect"))
    )
    (net (code "149") (name "unconnected-(IC9-NC2-Pad7)") (class "Default")
      (node (ref "IC9") (pin "7") (pinfunction "NC2_7") (pintype "no_connect"))
    )
    (net (code "150") (name "unconnected-(IC9-NC3-Pad8)") (class "Default")
      (node (ref "IC9") (pin "8") (pinfunction "NC3_8") (pintype "no_connect"))
    )
    (net (code "151") (name "unconnected-(IC9-NC4-Pad9)") (class "Default")
      (node (ref "IC9") (pin "9") (pinfunction "NC4_9") (pintype "no_connect"))
    )
    (net (code "152") (name "unconnected-(IC9-NC5-Pad10)") (class "Default")
      (node (ref "IC9") (pin "10") (pinfunction "NC5_10") (pintype "no_connect"))
    )
    (net (code "153") (name "unconnected-(IC9-NC6-Pad11)") (class "Default")
      (node (ref "IC9") (pin "11") (pinfunction "NC6_11") (pintype "no_connect"))
    )
    (net (code "154") (name "unconnected-(IC9-NC7-Pad12)") (class "Default")
      (node (ref "IC9") (pin "12") (pinfunction "NC7_12") (pintype "no_connect"))
    )
    (net (code "155") (name "unconnected-(IC9-SQW{slash}INT-Pad3)") (class "Default")
      (node (ref "IC9") (pin "3") (pinfunction "SQW/INT_3") (pintype "output"))
    )
    (net (code "156") (name "unconnected-(IC9-{slash}RST-Pad4)") (class "Default")
      (node (ref "IC9") (pin "4") (pinfunction "/RST_4") (pintype "passive"))
    )
    (net (code "157") (name "unconnected-(K1B-O-Pad5)") (class "Default")
      (node (ref "K1") (pin "5") (pinfunction "O_5") (pintype "passive"))
    )
    (net (code "158") (name "unconnected-(K2B-O-Pad5)") (class "Default")
      (node (ref "K2") (pin "5") (pinfunction "O_5") (pintype "passive"))
    )
    (net (code "159") (name "unconnected-(K3B-O-Pad5)") (class "Default")
      (node (ref "K3") (pin "5") (pinfunction "O_5") (pintype "passive"))
    )
    (net (code "160") (name "unconnected-(U$1-N.C.-Pad3)") (class "Default")
      (node (ref "U$1") (pin "3") (pinfunction "N.C._3") (pintype "passive"))
    )
    (net (code "161") (name "~{RST}") (class "Default")
      (node (ref "IC1") (pin "RESET") (pinfunction "RESET_RESET") (pintype "bidirectional"))
      (node (ref "SW13") (pin "2") (pinfunction "2_2") (pintype "bidirectional"))
    )
  )
)
